# tigor_mbed_rev_b_print.net
KiCad netlist of a schematic drawn in EAGLE
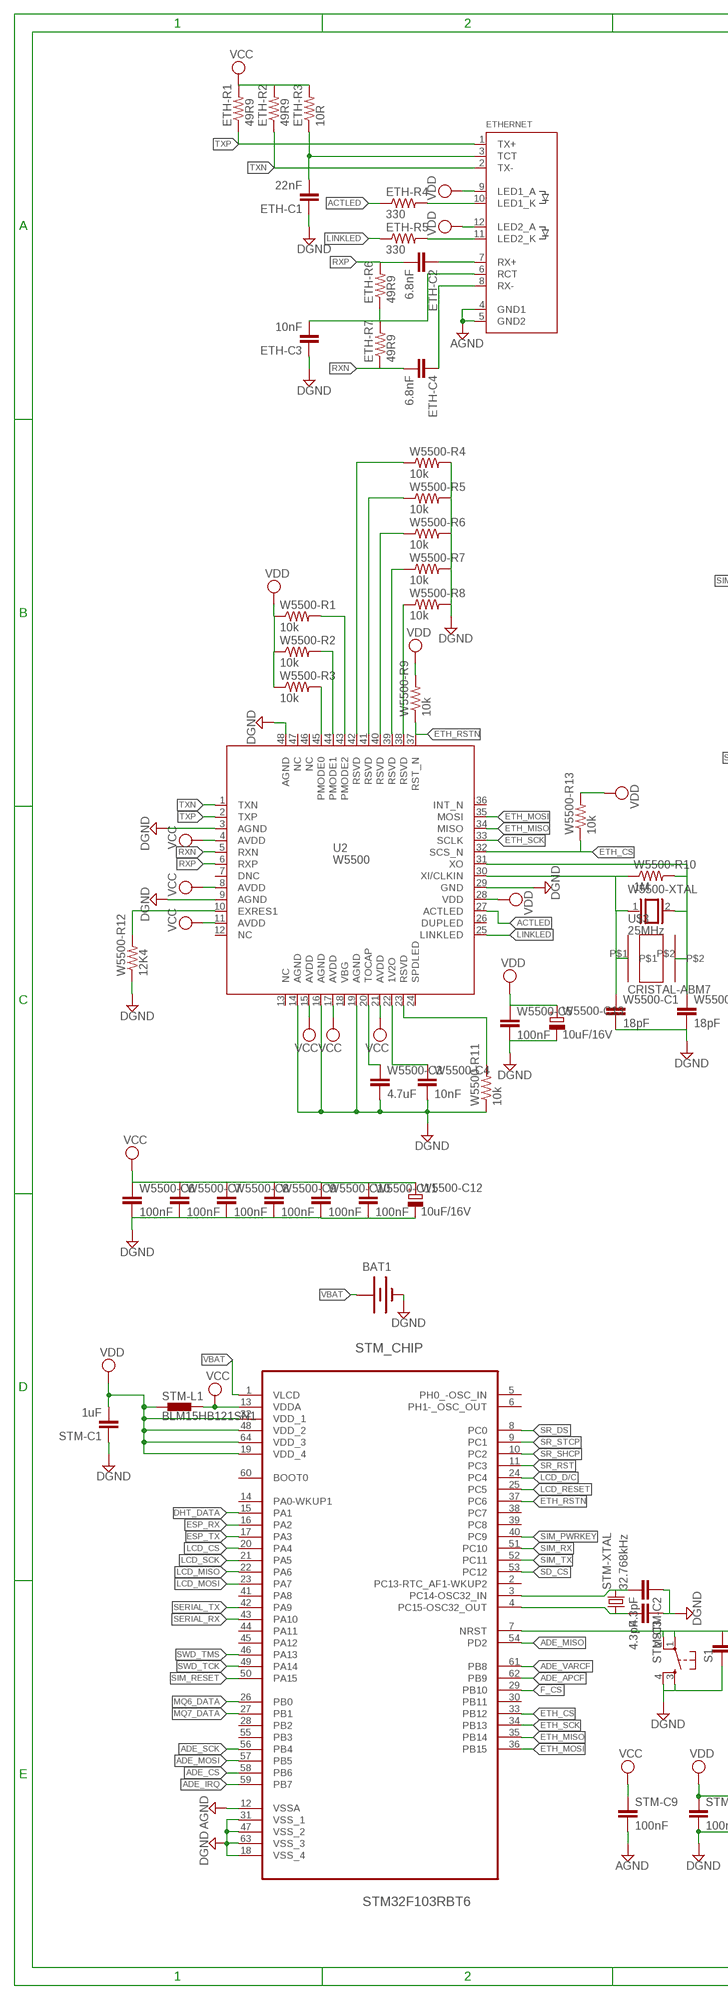
[diagram p0: schematic, sheet 1, part 1 of 2]
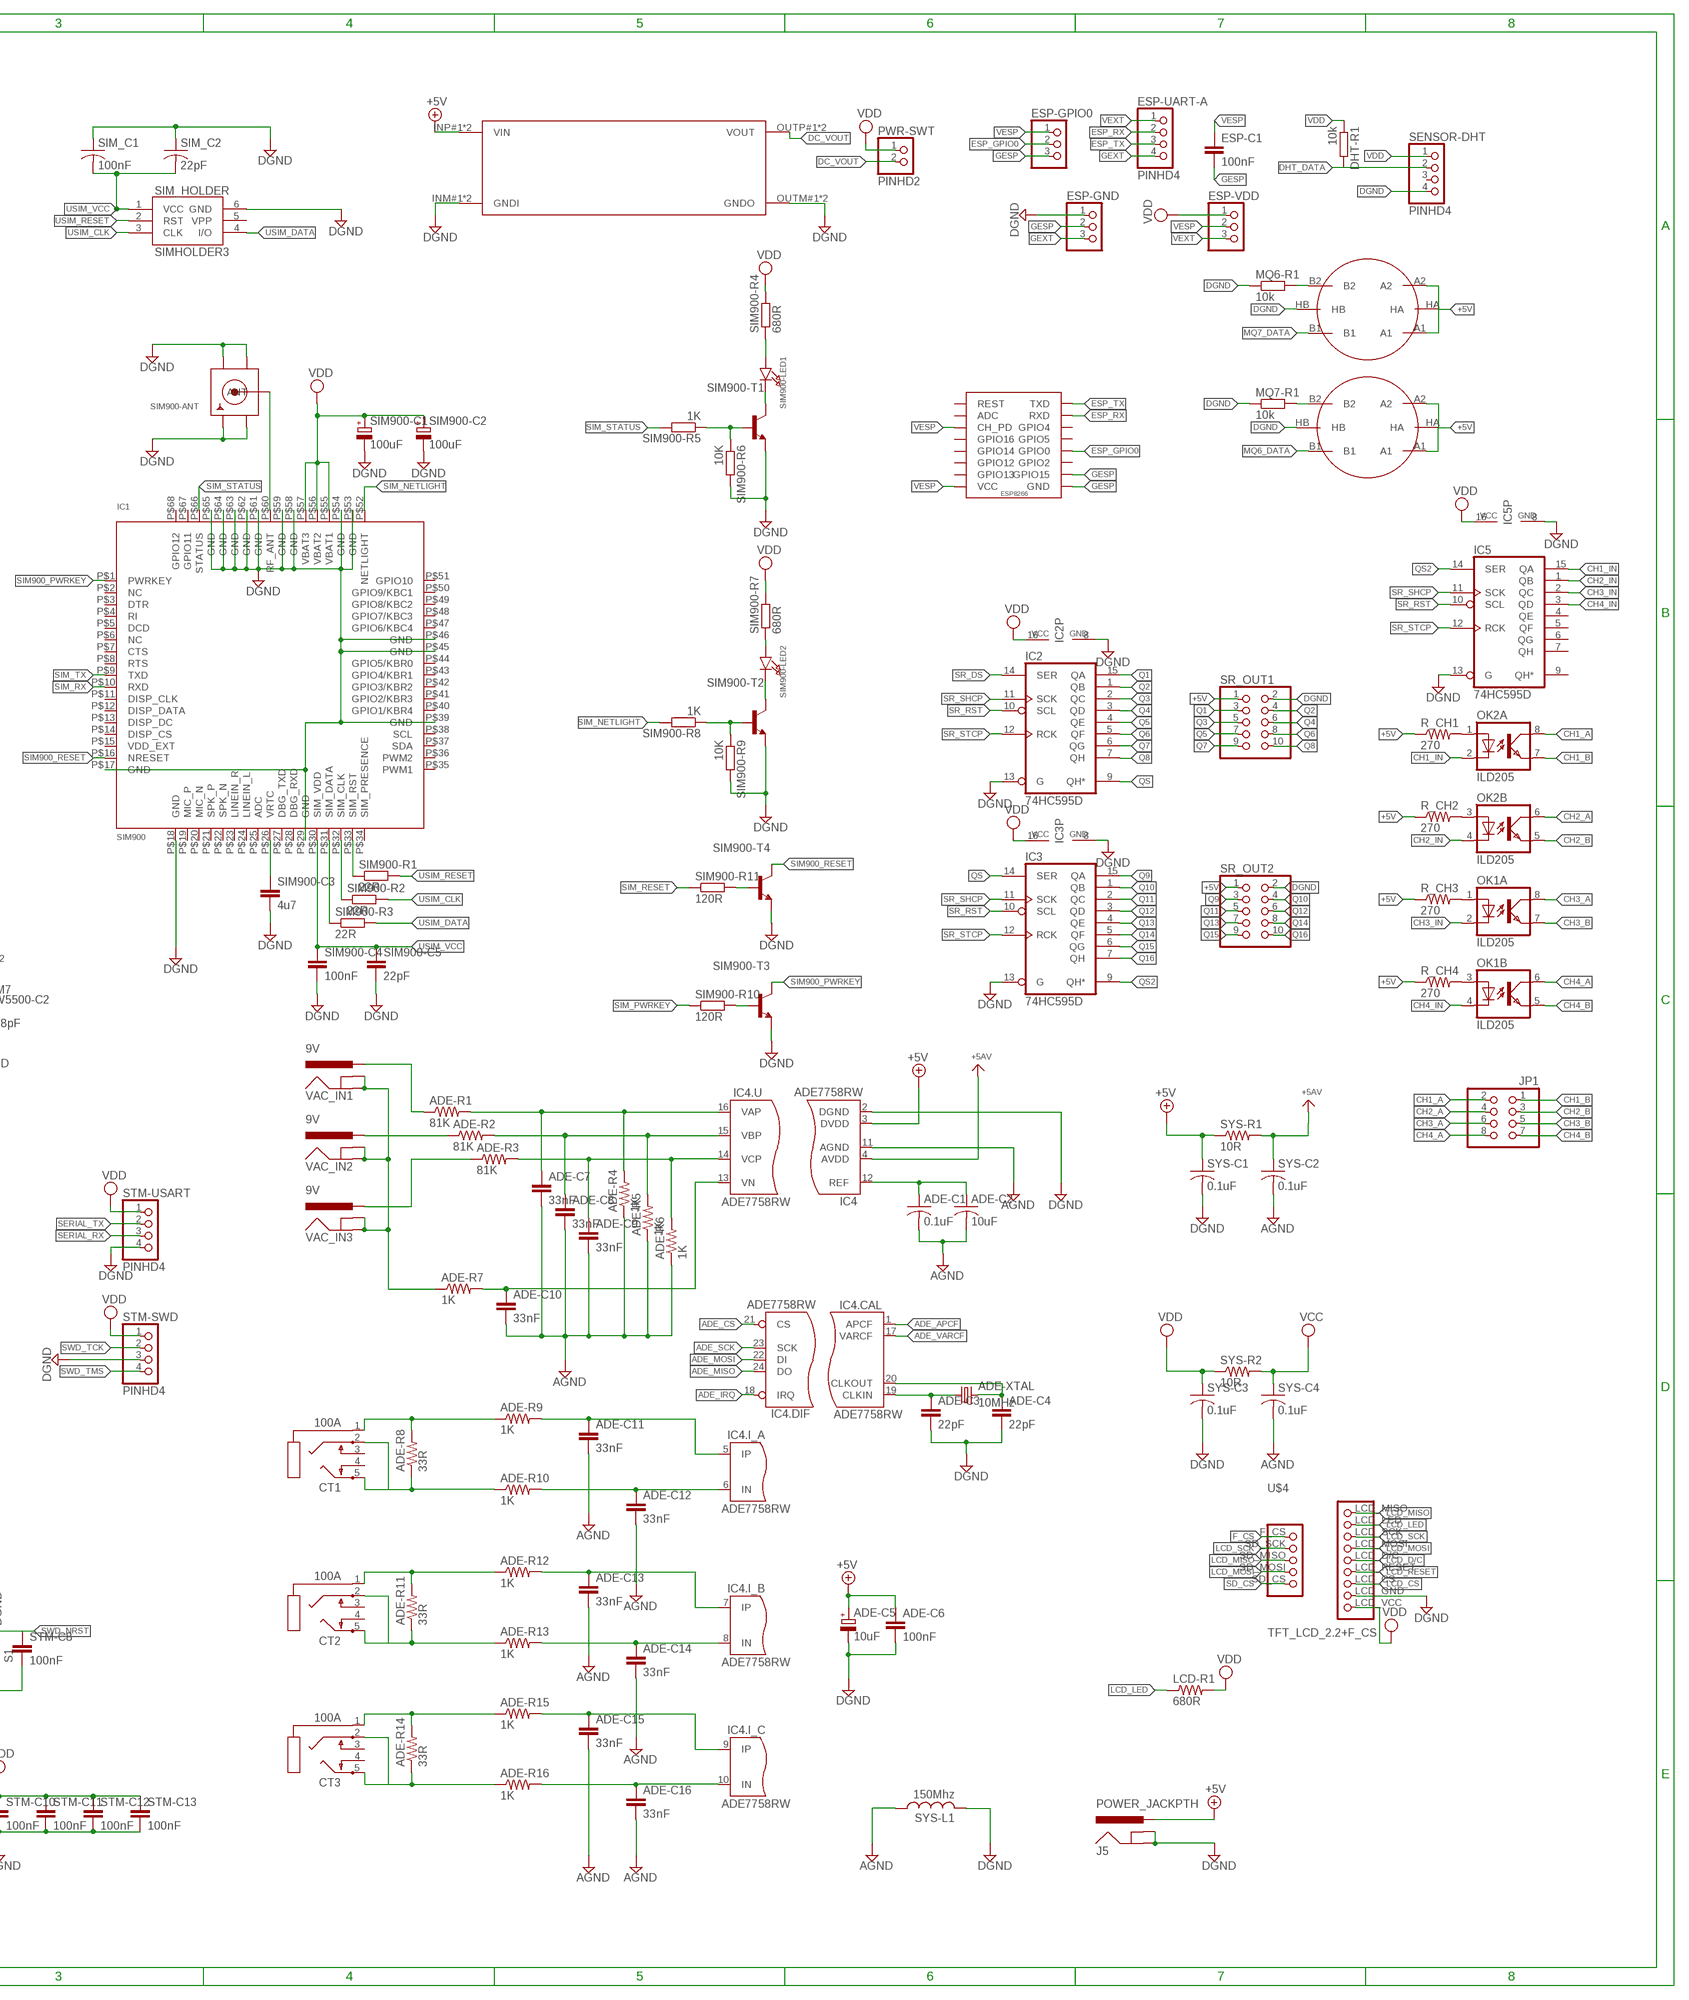
[diagram p1: schematic, sheet 1, part 2 of 2]

(export (version "E")
  (design (tool "Eeschema 10.0.6"))
  (components
    (comp (ref "ADE-C1")
      (value "0.1uF")
      (footprint "eagle-import:C0603@1")
      (libsource (lib "eagle-import") (part "C-USC0603"))
    )
    (comp (ref "ADE-C2")
      (value "10uF")
      (footprint "eagle-import:C0805K")
      (libsource (lib "eagle-import") (part "C-USC0805K"))
    )
    (comp (ref "ADE-C3")
      (value "22pF")
      (footprint "eagle-import:C0603")
      (libsource (lib "eagle-import") (part "C-EUC0603"))
    )
    (comp (ref "ADE-C4")
      (value "22pF")
      (footprint "eagle-import:C0603")
      (libsource (lib "eagle-import") (part "C-EUC0603"))
    )
    (comp (ref "ADE-C5")
      (value "10uF")
      (footprint "eagle-import:153CLV-0605")
      (libsource (lib "eagle-import") (part "CPOL-EU153CLV-0605"))
    )
    (comp (ref "ADE-C6")
      (value "100nF")
      (footprint "eagle-import:C0603")
      (libsource (lib "eagle-import") (part "C-EUC0603"))
    )
    (comp (ref "ADE-C7")
      (value "33nF")
      (footprint "eagle-import:0603-CAP")
      (libsource (lib "eagle-import") (part "CAP0603-CAP"))
    )
    (comp (ref "ADE-C8")
      (value "33nF")
      (footprint "eagle-import:0603-CAP")
      (libsource (lib "eagle-import") (part "CAP0603-CAP"))
    )
    (comp (ref "ADE-C9")
      (value "33nF")
      (footprint "eagle-import:0603-CAP")
      (libsource (lib "eagle-import") (part "CAP0603-CAP"))
    )
    (comp (ref "ADE-C10")
      (value "33nF")
      (footprint "eagle-import:0603-CAP")
      (libsource (lib "eagle-import") (part "CAP0603-CAP"))
    )
    (comp (ref "ADE-C11")
      (value "33nF")
      (footprint "eagle-import:0603-CAP")
      (libsource (lib "eagle-import") (part "CAP0603-CAP"))
    )
    (comp (ref "ADE-C12")
      (value "33nF")
      (footprint "eagle-import:0603-CAP")
      (libsource (lib "eagle-import") (part "CAP0603-CAP"))
    )
    (comp (ref "ADE-C13")
      (value "33nF")
      (footprint "eagle-import:0603-CAP")
      (libsource (lib "eagle-import") (part "CAP0603-CAP"))
    )
    (comp (ref "ADE-C14")
      (value "33nF")
      (footprint "eagle-import:0603-CAP")
      (libsource (lib "eagle-import") (part "CAP0603-CAP"))
    )
    (comp (ref "ADE-C15")
      (value "33nF")
      (footprint "eagle-import:0603-CAP")
      (libsource (lib "eagle-import") (part "CAP0603-CAP"))
    )
    (comp (ref "ADE-C16")
      (value "33nF")
      (footprint "eagle-import:0603-CAP")
      (libsource (lib "eagle-import") (part "CAP0603-CAP"))
    )
    (comp (ref "ADE-R1")
      (value "81K")
      (footprint "eagle-import:0603-RES")
      (libsource (lib "eagle-import") (part "RESISTOR0603-RES"))
    )
    (comp (ref "ADE-R2")
      (value "81K")
      (footprint "eagle-import:0603-RES")
      (libsource (lib "eagle-import") (part "RESISTOR0603-RES"))
    )
    (comp (ref "ADE-R3")
      (value "81K")
      (footprint "eagle-import:0603-RES")
      (libsource (lib "eagle-import") (part "RESISTOR0603-RES"))
    )
    (comp (ref "ADE-R4")
      (value "1K")
      (footprint "eagle-import:0603-RES")
      (libsource (lib "eagle-import") (part "RESISTOR0603-RES"))
    )
    (comp (ref "ADE-R5")
      (value "1K")
      (footprint "eagle-import:0603-RES")
      (libsource (lib "eagle-import") (part "RESISTOR0603-RES"))
    )
    (comp (ref "ADE-R6")
      (value "1K")
      (footprint "eagle-import:0603-RES")
      (libsource (lib "eagle-import") (part "RESISTOR0603-RES"))
    )
    (comp (ref "ADE-R7")
      (value "1K")
      (footprint "eagle-import:0603-RES")
      (libsource (lib "eagle-import") (part "RESISTOR0603-RES"))
    )
    (comp (ref "ADE-R8")
      (value "33R")
      (footprint "eagle-import:0603-RES")
      (libsource (lib "eagle-import") (part "RESISTOR0603-RES"))
    )
    (comp (ref "ADE-R9")
      (value "1K")
      (footprint "eagle-import:0603-RES")
      (libsource (lib "eagle-import") (part "RESISTOR0603-RES"))
    )
    (comp (ref "ADE-R10")
      (value "1K")
      (footprint "eagle-import:0603-RES")
      (libsource (lib "eagle-import") (part "RESISTOR0603-RES"))
    )
    (comp (ref "ADE-R11")
      (value "33R")
      (footprint "eagle-import:0603-RES")
      (libsource (lib "eagle-import") (part "RESISTOR0603-RES"))
    )
    (comp (ref "ADE-R12")
      (value "1K")
      (footprint "eagle-import:0603-RES")
      (libsource (lib "eagle-import") (part "RESISTOR0603-RES"))
    )
    (comp (ref "ADE-R13")
      (value "1K")
      (footprint "eagle-import:0603-RES")
      (libsource (lib "eagle-import") (part "RESISTOR0603-RES"))
    )
    (comp (ref "ADE-R14")
      (value "33R")
      (footprint "eagle-import:0603-RES")
      (libsource (lib "eagle-import") (part "RESISTOR0603-RES"))
    )
    (comp (ref "ADE-R15")
      (value "1K")
      (footprint "eagle-import:0603-RES")
      (libsource (lib "eagle-import") (part "RESISTOR0603-RES"))
    )
    (comp (ref "ADE-R16")
      (value "1K")
      (footprint "eagle-import:0603-RES")
      (libsource (lib "eagle-import") (part "RESISTOR0603-RES"))
    )
    (comp (ref "ADE-XTAL")
      (value "10MHz")
      (footprint "eagle-import:HC49US")
      (libsource (lib "eagle-import") (part "CRYSTALHC49US"))
    )
    (comp (ref "BAT1")
      (value "BATTERY20PTH")
      (footprint "eagle-import:BATTCOM_20MM_PTH")
      (libsource (lib "eagle-import") (part "BATTERY20PTH"))
    )
    (comp (ref "CT1")
      (value "100A")
      (footprint "eagle-import:STX3100")
      (libsource (lib "eagle-import") (part "AUDIO_STEREOJACK"))
    )
    (comp (ref "CT2")
      (value "100A")
      (footprint "eagle-import:STX3100")
      (libsource (lib "eagle-import") (part "AUDIO_STEREOJACK"))
    )
    (comp (ref "CT3")
      (value "100A")
      (footprint "eagle-import:STX3100")
      (libsource (lib "eagle-import") (part "AUDIO_STEREOJACK"))
    )
    (comp (ref "DCDC-3.5V")
      (value "DCDCMODULE_SMALL")
      (footprint "eagle-import:DCDCMODULE-SMALL")
      (libsource (lib "eagle-import") (part "DCDCMODULE_SMALL"))
    )
    (comp (ref "DHT-R1")
      (value "10k")
      (footprint "eagle-import:R0603")
      (libsource (lib "eagle-import") (part "resistor_R-EU_R0603"))
    )
    (comp (ref "ESP-C1")
      (value "100nF")
      (footprint "eagle-import:C0603")
      (libsource (lib "eagle-import") (part "C-EUC0603"))
    )
    (comp (ref "ESP-GND")
      (value "PINHD-1X3")
      (footprint "eagle-import:1X03")
      (libsource (lib "eagle-import") (part "PINHD-1X3"))
    )
    (comp (ref "ESP-GPIO0")
      (value "PINHD-1X3")
      (footprint "eagle-import:1X03")
      (libsource (lib "eagle-import") (part "PINHD-1X3"))
    )
    (comp (ref "ESP-UART-A")
      (value "PINHD4")
      (footprint "eagle-import:PINHD4")
      (libsource (lib "eagle-import") (part "PINHD4"))
    )
    (comp (ref "ESP-VDD")
      (value "PINHD-1X3")
      (footprint "eagle-import:1X03")
      (libsource (lib "eagle-import") (part "PINHD-1X3"))
    )
    (comp (ref "ETH-C1")
      (value "22nF")
      (footprint "eagle-import:C0603")
      (libsource (lib "eagle-import") (part "C-EUC0603"))
    )
    (comp (ref "ETH-C2")
      (value "6.8nF")
      (footprint "eagle-import:C0603")
      (libsource (lib "eagle-import") (part "C-EUC0603"))
    )
    (comp (ref "ETH-C3")
      (value "10nF")
      (footprint "eagle-import:C0603")
      (libsource (lib "eagle-import") (part "C-EUC0603"))
    )
    (comp (ref "ETH-C4")
      (value "6.8nF")
      (footprint "eagle-import:C0603")
      (libsource (lib "eagle-import") (part "C-EUC0603"))
    )
    (comp (ref "ETH-R1")
      (value "49R9")
      (footprint "eagle-import:R0603")
      (libsource (lib "eagle-import") (part "R-US_R0603"))
    )
    (comp (ref "ETH-R2")
      (value "49R9")
      (footprint "eagle-import:R0603")
      (libsource (lib "eagle-import") (part "R-US_R0603"))
    )
    (comp (ref "ETH-R3")
      (value "10R")
      (footprint "eagle-import:R0603")
      (libsource (lib "eagle-import") (part "R-US_R0603"))
    )
    (comp (ref "ETH-R4")
      (value "330")
      (footprint "eagle-import:R0603")
      (libsource (lib "eagle-import") (part "R-US_R0603"))
    )
    (comp (ref "ETH-R5")
      (value "330")
      (footprint "eagle-import:R0603")
      (libsource (lib "eagle-import") (part "R-US_R0603"))
    )
    (comp (ref "ETH-R6")
      (value "49R9")
      (footprint "eagle-import:R0603")
      (libsource (lib "eagle-import") (part "R-US_R0603"))
    )
    (comp (ref "ETH-R7")
      (value "49R9")
      (footprint "eagle-import:R0603")
      (libsource (lib "eagle-import") (part "R-US_R0603"))
    )
    (comp (ref "ETHERNET")
      (value "RJ45J0026D21BNL")
      (footprint "eagle-import:RJ45_PULSEJACK")
      (libsource (lib "eagle-import") (part "RJ45J0026D21BNL"))
    )
    (comp (ref "IC1")
      (value "SIM900")
      (footprint "eagle-import:SIM900_SMT")
      (libsource (lib "eagle-import") (part "GSM_SIM900_LITERAL"))
    )
    (comp (ref "IC2")
      (value "74HC595D")
      (footprint "eagle-import:SO16")
      (libsource (lib "eagle-import") (part "74595DHC"))
    )
    (comp (ref "IC3")
      (value "74HC595D")
      (footprint "eagle-import:SO16")
      (libsource (lib "eagle-import") (part "74595DHC"))
    )
    (comp (ref "IC4")
      (value "ADE7758RW")
      (footprint "eagle-import:SOIC24")
      (libsource (lib "eagle-import") (part "ADE7758RW"))
    )
    (comp (ref "IC5")
      (value "74HC595D")
      (footprint "eagle-import:SO16")
      (libsource (lib "eagle-import") (part "74595DHC"))
    )
    (comp (ref "J5")
      (value "POWER_JACKPTH")
      (footprint "eagle-import:POWER_JACK_PTH")
      (libsource (lib "eagle-import") (part "POWER_JACKPTH"))
    )
    (comp (ref "JP1")
      (value "PINHD-2X4")
      (footprint "eagle-import:2X04")
      (libsource (lib "eagle-import") (part "PINHD-2X4"))
    )
    (comp (ref "LCD-R1")
      (value "680R")
      (footprint "eagle-import:0603-RES")
      (libsource (lib "eagle-import") (part "RESISTOR0603-RES"))
    )
    (comp (ref "MQ6-R1")
      (value "10k")
      (footprint "eagle-import:R0603")
      (libsource (lib "eagle-import") (part "resistor_R-EU_R0603"))
    )
    (comp (ref "MQ7-R1")
      (value "10k")
      (footprint "eagle-import:R0603")
      (libsource (lib "eagle-import") (part "resistor_R-EU_R0603"))
    )
    (comp (ref "OK1")
      (value "ILD205")
      (footprint "eagle-import:SOIC08")
      (fields (field (name "MF") "VISHAY/TELEFUNKEN") (field (name "MPN") "ILD205T"))
      (libsource (lib "eagle-import") (part "ILD205"))
    )
    (comp (ref "OK2")
      (value "ILD205")
      (footprint "eagle-import:SOIC08")
      (fields (field (name "MF") "VISHAY/TELEFUNKEN") (field (name "MPN") "ILD205T"))
      (libsource (lib "eagle-import") (part "ILD205"))
    )
    (comp (ref "PWR-SWT")
      (value "PINHD2")
      (footprint "eagle-import:PINHD2")
      (libsource (lib "eagle-import") (part "PINHD2"))
    )
    (comp (ref "R_CH1")
      (value "270")
      (footprint "eagle-import:0603-RES")
      (libsource (lib "eagle-import") (part "RESISTOR0603-RES"))
    )
    (comp (ref "R_CH2")
      (value "270")
      (footprint "eagle-import:0603-RES")
      (libsource (lib "eagle-import") (part "RESISTOR0603-RES"))
    )
    (comp (ref "R_CH3")
      (value "270")
      (footprint "eagle-import:0603-RES")
      (libsource (lib "eagle-import") (part "RESISTOR0603-RES"))
    )
    (comp (ref "R_CH4")
      (value "270")
      (footprint "eagle-import:0603-RES")
      (libsource (lib "eagle-import") (part "RESISTOR0603-RES"))
    )
    (comp (ref "S1")
      (value "TAC_SWITCHPTH")
      (footprint "eagle-import:TACTILE-PTH")
      (libsource (lib "eagle-import") (part "TAC_SWITCHPTH"))
    )
    (comp (ref "SENSOR-DHT")
      (value "PINHD4")
      (footprint "eagle-import:PINHD4")
      (libsource (lib "eagle-import") (part "PINHD4"))
    )
    (comp (ref "SENSOR-MQ6")
      (value "METHANE_SENSOR")
      (footprint "eagle-import:MQ-3")
      (libsource (lib "eagle-import") (part "METHANE_SENSOR"))
    )
    (comp (ref "SENSOR-MQ7")
      (value "METHANE_SENSOR")
      (footprint "eagle-import:MQ-3")
      (libsource (lib "eagle-import") (part "METHANE_SENSOR"))
    )
    (comp (ref "SIM900-ANT")
      (value "SMACONNECTOR")
      (footprint "eagle-import:SMA90_DIP")
      (libsource (lib "eagle-import") (part "SMACONNECTOR"))
    )
    (comp (ref "SIM900-C1")
      (value "100uF")
      (footprint "eagle-import:153CLV-0605")
      (libsource (lib "eagle-import") (part "CPOL-EU153CLV-0605"))
    )
    (comp (ref "SIM900-C2")
      (value "100uF")
      (footprint "eagle-import:153CLV-0605")
      (libsource (lib "eagle-import") (part "CPOL-EU153CLV-0605"))
    )
    (comp (ref "SIM900-C3")
      (value "4u7")
      (footprint "eagle-import:C0603")
      (libsource (lib "eagle-import") (part "C-EUC0603"))
    )
    (comp (ref "SIM900-C4")
      (value "100nF")
      (footprint "eagle-import:C0603")
      (libsource (lib "eagle-import") (part "C-EUC0603"))
    )
    (comp (ref "SIM900-C5")
      (value "22pF")
      (footprint "eagle-import:C0603")
      (libsource (lib "eagle-import") (part "C-EUC0603"))
    )
    (comp (ref "SIM900-LED1")
      (value "LED0805_NOOUTLINE")
      (footprint "eagle-import:CHIPLED_0805_NOOUTLINE")
      (libsource (lib "eagle-import") (part "LED0805_NOOUTLINE"))
    )
    (comp (ref "SIM900-LED2")
      (value "LED0805_NOOUTLINE")
      (footprint "eagle-import:CHIPLED_0805_NOOUTLINE")
      (libsource (lib "eagle-import") (part "LED0805_NOOUTLINE"))
    )
    (comp (ref "SIM900-R1")
      (value "22R")
      (footprint "eagle-import:R0603")
      (libsource (lib "eagle-import") (part "R-EU_R0603"))
    )
    (comp (ref "SIM900-R2")
      (value "22R")
      (footprint "eagle-import:R0603")
      (libsource (lib "eagle-import") (part "R-EU_R0603"))
    )
    (comp (ref "SIM900-R3")
      (value "22R")
      (footprint "eagle-import:R0603")
      (libsource (lib "eagle-import") (part "R-EU_R0603"))
    )
    (comp (ref "SIM900-R4")
      (value "680R")
      (footprint "eagle-import:R0603")
      (libsource (lib "eagle-import") (part "R-EU_R0603"))
    )
    (comp (ref "SIM900-R5")
      (value "1K")
      (footprint "eagle-import:R0603")
      (libsource (lib "eagle-import") (part "R-EU_R0603"))
    )
    (comp (ref "SIM900-R6")
      (value "10K")
      (footprint "eagle-import:R0603")
      (libsource (lib "eagle-import") (part "R-EU_R0603"))
    )
    (comp (ref "SIM900-R7")
      (value "680R")
      (footprint "eagle-import:R0603")
      (libsource (lib "eagle-import") (part "R-EU_R0603"))
    )
    (comp (ref "SIM900-R8")
      (value "1K")
      (footprint "eagle-import:R0603")
      (libsource (lib "eagle-import") (part "R-EU_R0603"))
    )
    (comp (ref "SIM900-R9")
      (value "10K")
      (footprint "eagle-import:R0603")
      (libsource (lib "eagle-import") (part "R-EU_R0603"))
    )
    (comp (ref "SIM900-R10")
      (value "120R")
      (footprint "eagle-import:R0603")
      (libsource (lib "eagle-import") (part "resistor_R-EU_R0603"))
    )
    (comp (ref "SIM900-R11")
      (value "120R")
      (footprint "eagle-import:R0603")
      (libsource (lib "eagle-import") (part "resistor_R-EU_R0603"))
    )
    (comp (ref "SIM900-T1")
      (value "MMBT2222ALT1-NPN-SOT23-BEC")
      (footprint "eagle-import:SOT23-BEC")
      (libsource (lib "eagle-import") (part "-NPN-SOT23-BECMMBT2222ALT1"))
    )
    (comp (ref "SIM900-T2")
      (value "MMBT2222ALT1-NPN-SOT23-BEC")
      (footprint "eagle-import:SOT23-BEC")
      (libsource (lib "eagle-import") (part "-NPN-SOT23-BECMMBT2222ALT1"))
    )
    (comp (ref "SIM900-T3")
      (value "MMBT2222ALT1-NPN-SOT23-BEC")
      (footprint "eagle-import:SOT23-BEC")
      (libsource (lib "eagle-import") (part "transistor-neu-to92_-NPN-SOT23-BECMMBT2222ALT1"))
    )
    (comp (ref "SIM900-T4")
      (value "MMBT2222ALT1-NPN-SOT23-BEC")
      (footprint "eagle-import:SOT23-BEC")
      (libsource (lib "eagle-import") (part "transistor-neu-to92_-NPN-SOT23-BECMMBT2222ALT1"))
    )
    (comp (ref "SIM_C1")
      (value "100nF")
      (footprint "eagle-import:C0603K")
      (libsource (lib "eagle-import") (part "C-USC0603K"))
    )
    (comp (ref "SIM_C2")
      (value "22pF")
      (footprint "eagle-import:C0603K")
      (libsource (lib "eagle-import") (part "C-USC0603K"))
    )
    (comp (ref "SIM_HOLDER")
      (value "SIMHOLDER3")
      (footprint "eagle-import:SIMHOLDER3")
      (libsource (lib "eagle-import") (part "SIMHOLDER3"))
    )
    (comp (ref "SR_OUT1")
      (value "PINHD-2X5/90")
      (footprint "eagle-import:2X05_90")
      (libsource (lib "eagle-import") (part "PINHD-2X5/90"))
    )
    (comp (ref "SR_OUT2")
      (value "PINHD-2X5/90")
      (footprint "eagle-import:2X05_90")
      (libsource (lib "eagle-import") (part "PINHD-2X5/90"))
    )
    (comp (ref "STM-C1")
      (value "1uF")
      (footprint "eagle-import:C0603")
      (libsource (lib "eagle-import") (part "C-EUC0603"))
    )
    (comp (ref "STM-C2")
      (value "4.3pF")
      (footprint "eagle-import:C0603")
      (libsource (lib "eagle-import") (part "C-EUC0603"))
    )
    (comp (ref "STM-C3")
      (value "4.3pF")
      (footprint "eagle-import:C0603")
      (libsource (lib "eagle-import") (part "C-EUC0603"))
    )
    (comp (ref "STM-C8")
      (value "100nF")
      (footprint "eagle-import:C0603")
      (libsource (lib "eagle-import") (part "C-EUC0603"))
    )
    (comp (ref "STM-C9")
      (value "100nF")
      (footprint "eagle-import:C0603")
      (libsource (lib "eagle-import") (part "C-EUC0603"))
    )
    (comp (ref "STM-C10")
      (value "100nF")
      (footprint "eagle-import:C0603")
      (libsource (lib "eagle-import") (part "C-EUC0603"))
    )
    (comp (ref "STM-C11")
      (value "100nF")
      (footprint "eagle-import:C0603")
      (libsource (lib "eagle-import") (part "C-EUC0603"))
    )
    (comp (ref "STM-C12")
      (value "100nF")
      (footprint "eagle-import:C0603")
      (libsource (lib "eagle-import") (part "C-EUC0603"))
    )
    (comp (ref "STM-C13")
      (value "100nF")
      (footprint "eagle-import:C0603")
      (libsource (lib "eagle-import") (part "C-EUC0603"))
    )
    (comp (ref "STM-L1")
      (value "BLM15HB121SN1")
      (footprint "eagle-import:0402")
      (libsource (lib "eagle-import") (part "BLM15HB121SN1"))
    )
    (comp (ref "STM-SWD")
      (value "PINHD4")
      (footprint "eagle-import:PINHD4")
      (libsource (lib "eagle-import") (part "PINHD4"))
    )
    (comp (ref "STM-USART")
      (value "PINHD4")
      (footprint "eagle-import:PINHD4")
      (libsource (lib "eagle-import") (part "PINHD4"))
    )
    (comp (ref "STM-XTAL")
      (value "32.768kHz")
      (footprint "eagle-import:TC26H")
      (libsource (lib "eagle-import") (part "CRYSTALTC26H"))
    )
    (comp (ref "STM_CHIP")
      (value "STM32F103RBT6")
      (footprint "eagle-import:QFP50P1200X1200X160-64N")
      (fields (field (name "MPN") "STM32L152RBT6"))
      (libsource (lib "eagle-import") (part "STM32L152RBT6"))
    )
    (comp (ref "SYS-C1")
      (value "0.1uF")
      (footprint "eagle-import:C0603@1")
      (libsource (lib "eagle-import") (part "C-USC0603"))
    )
    (comp (ref "SYS-C2")
      (value "0.1uF")
      (footprint "eagle-import:C0603@1")
      (libsource (lib "eagle-import") (part "C-USC0603"))
    )
    (comp (ref "SYS-C3")
      (value "0.1uF")
      (footprint "eagle-import:C0603@1")
      (libsource (lib "eagle-import") (part "C-USC0603"))
    )
    (comp (ref "SYS-C4")
      (value "0.1uF")
      (footprint "eagle-import:C0603@1")
      (libsource (lib "eagle-import") (part "C-USC0603"))
    )
    (comp (ref "SYS-L1")
      (value "150Mhz")
      (footprint "eagle-import:POWER-CHOKE_WE-TPC")
      (libsource (lib "eagle-import") (part "L-USWE-TPC"))
    )
    (comp (ref "SYS-R1")
      (value "10R")
      (footprint "eagle-import:0603-RES")
      (libsource (lib "eagle-import") (part "RESISTOR0603-RES"))
    )
    (comp (ref "SYS-R2")
      (value "10R")
      (footprint "eagle-import:0603-RES")
      (libsource (lib "eagle-import") (part "RESISTOR0603-RES"))
    )
    (comp (ref "U$3")
      (value "CRISTAL-ABM7")
      (footprint "eagle-import:CRISTAL-ABM7")
      (libsource (lib "eagle-import") (part "CRISTAL-ABM7"))
    )
    (comp (ref "U$4")
      (value "TFT_LCD_2.2+F_CS")
      (footprint "eagle-import:TFT_LCD_2.2+F_CS")
      (libsource (lib "eagle-import") (part "TFT_LCD_2.2+F_CS"))
    )
    (comp (ref "U$5")
      (value "ESP8266WI12")
      (footprint "eagle-import:WI12")
      (libsource (lib "eagle-import") (part "ESP8266WI12"))
    )
    (comp (ref "U2")
      (value "W5500")
      (footprint "eagle-import:W5500")
      (libsource (lib "eagle-import") (part "W5500"))
    )
    (comp (ref "VAC_IN1")
      (value "9V")
      (footprint "eagle-import:POWER_JACK_PTH")
      (libsource (lib "eagle-import") (part "POWER_JACKPTH"))
    )
    (comp (ref "VAC_IN2")
      (value "9V")
      (footprint "eagle-import:POWER_JACK_PTH")
      (libsource (lib "eagle-import") (part "POWER_JACKPTH"))
    )
    (comp (ref "VAC_IN3")
      (value "9V")
      (footprint "eagle-import:POWER_JACK_PTH")
      (libsource (lib "eagle-import") (part "POWER_JACKPTH"))
    )
    (comp (ref "W5500-C1")
      (value "18pF")
      (footprint "eagle-import:C0603")
      (libsource (lib "eagle-import") (part "C-EUC0603"))
    )
    (comp (ref "W5500-C2")
      (value "18pF")
      (footprint "eagle-import:C0603")
      (libsource (lib "eagle-import") (part "C-EUC0603"))
    )
    (comp (ref "W5500-C3")
      (value "4.7uF")
      (footprint "eagle-import:C0603")
      (libsource (lib "eagle-import") (part "C-EUC0603"))
    )
    (comp (ref "W5500-C4")
      (value "10nF")
      (footprint "eagle-import:C0603")
      (libsource (lib "eagle-import") (part "C-EUC0603"))
    )
    (comp (ref "W5500-C5")
      (value "100nF")
      (footprint "eagle-import:C0603")
      (libsource (lib "eagle-import") (part "C-EUC0603"))
    )
    (comp (ref "W5500-C6")
      (value "100nF")
      (footprint "eagle-import:C0603")
      (libsource (lib "eagle-import") (part "C-EUC0603"))
    )
    (comp (ref "W5500-C7")
      (value "100nF")
      (footprint "eagle-import:C0603")
      (libsource (lib "eagle-import") (part "C-EUC0603"))
    )
    (comp (ref "W5500-C8")
      (value "100nF")
      (footprint "eagle-import:C0603")
      (libsource (lib "eagle-import") (part "C-EUC0603"))
    )
    (comp (ref "W5500-C9")
      (value "100nF")
      (footprint "eagle-import:C0603")
      (libsource (lib "eagle-import") (part "C-EUC0603"))
    )
    (comp (ref "W5500-C10")
      (value "100nF")
      (footprint "eagle-import:C0603")
      (libsource (lib "eagle-import") (part "C-EUC0603"))
    )
    (comp (ref "W5500-C11")
      (value "100nF")
      (footprint "eagle-import:C0603")
      (libsource (lib "eagle-import") (part "C-EUC0603"))
    )
    (comp (ref "W5500-C12")
      (value "10uF/16V")
      (footprint "eagle-import:153CLV-0605")
      (libsource (lib "eagle-import") (part "CPOL-EU153CLV-0605"))
    )
    (comp (ref "W5500-C13")
      (value "10uF/16V")
      (footprint "eagle-import:153CLV-0605")
      (libsource (lib "eagle-import") (part "CPOL-EU153CLV-0605"))
    )
    (comp (ref "W5500-R1")
      (value "10k")
      (footprint "eagle-import:R0603")
      (libsource (lib "eagle-import") (part "R-US_R0603"))
    )
    (comp (ref "W5500-R2")
      (value "10k")
      (footprint "eagle-import:R0603")
      (libsource (lib "eagle-import") (part "R-US_R0603"))
    )
    (comp (ref "W5500-R3")
      (value "10k")
      (footprint "eagle-import:R0603")
      (libsource (lib "eagle-import") (part "R-US_R0603"))
    )
    (comp (ref "W5500-R4")
      (value "10k")
      (footprint "eagle-import:R0603")
      (libsource (lib "eagle-import") (part "R-US_R0603"))
    )
    (comp (ref "W5500-R5")
      (value "10k")
      (footprint "eagle-import:R0603")
      (libsource (lib "eagle-import") (part "R-US_R0603"))
    )
    (comp (ref "W5500-R6")
      (value "10k")
      (footprint "eagle-import:R0603")
      (libsource (lib "eagle-import") (part "R-US_R0603"))
    )
    (comp (ref "W5500-R7")
      (value "10k")
      (footprint "eagle-import:R0603")
      (libsource (lib "eagle-import") (part "R-US_R0603"))
    )
    (comp (ref "W5500-R8")
      (value "10k")
      (footprint "eagle-import:R0603")
      (libsource (lib "eagle-import") (part "R-US_R0603"))
    )
    (comp (ref "W5500-R9")
      (value "10k")
      (footprint "eagle-import:R0603")
      (libsource (lib "eagle-import") (part "R-US_R0603"))
    )
    (comp (ref "W5500-R10")
      (value "1M")
      (footprint "eagle-import:R0603")
      (libsource (lib "eagle-import") (part "R-US_R0603"))
    )
    (comp (ref "W5500-R11")
      (value "10k")
      (footprint "eagle-import:R0603")
      (libsource (lib "eagle-import") (part "R-US_R0603"))
    )
    (comp (ref "W5500-R12")
      (value "12K4")
      (footprint "eagle-import:R0805")
      (libsource (lib "eagle-import") (part "R-US_R0805"))
    )
    (comp (ref "W5500-R13")
      (value "10k")
      (footprint "eagle-import:R0603")
      (libsource (lib "eagle-import") (part "R-US_R0603"))
    )
    (comp (ref "W5500-XTAL")
      (value "25MHz")
      (footprint "eagle-import:QS")
      (libsource (lib "eagle-import") (part "XTAL/S"))
    )
  )
  (nets
    (net (code "1") (name "+5AV") (class "Default")
      (node (ref "IC4") (pin "4") (pinfunction "AVDD_4") (pintype "power_in"))
      (node (ref "SYS-C2") (pin "1") (pinfunction "1_1") (pintype "passive"))
      (node (ref "SYS-R1") (pin "2") (pinfunction "2_2") (pintype "passive"))
    )
    (net (code "2") (name "+5V") (class "Default")
      (node (ref "ADE-C5") (pin "+") (pinfunction "+_+") (pintype "passive"))
      (node (ref "ADE-C6") (pin "1") (pinfunction "1_1") (pintype "passive"))
      (node (ref "DCDC-3.5V") (pin "INP#1") (pinfunction "VIN_INP#1") (pintype "bidirectional"))
      (node (ref "DCDC-3.5V") (pin "INP#2") (pinfunction "VIN_INP#2") (pintype "bidirectional"))
      (node (ref "IC4") (pin "3") (pinfunction "DVDD_3") (pintype "power_in"))
      (node (ref "J5") (pin "PWR") (pinfunction "PWR_PWR") (pintype "bidirectional"))
      (node (ref "R_CH1") (pin "1") (pinfunction "1_1") (pintype "passive"))
      (node (ref "R_CH2") (pin "1") (pinfunction "1_1") (pintype "passive"))
      (node (ref "R_CH3") (pin "1") (pinfunction "1_1") (pintype "passive"))
      (node (ref "R_CH4") (pin "1") (pinfunction "1_1") (pintype "passive"))
      (node (ref "SENSOR-MQ6") (pin "A1") (pinfunction "A1_A1") (pintype "bidirectional"))
      (node (ref "SENSOR-MQ6") (pin "A2") (pinfunction "A2_A2") (pintype "bidirectional"))
      (node (ref "SENSOR-MQ6") (pin "HA") (pinfunction "HA_HA") (pintype "bidirectional"))
      (node (ref "SENSOR-MQ7") (pin "A1") (pinfunction "A1_A1") (pintype "bidirectional"))
      (node (ref "SENSOR-MQ7") (pin "A2") (pinfunction "A2_A2") (pintype "bidirectional"))
      (node (ref "SENSOR-MQ7") (pin "HA") (pinfunction "HA_HA") (pintype "bidirectional"))
      (node (ref "SR_OUT1") (pin "1") (pinfunction "1_1") (pintype "passive"))
      (node (ref "SR_OUT2") (pin "1") (pinfunction "1_1") (pintype "passive"))
      (node (ref "SYS-C1") (pin "1") (pinfunction "1_1") (pintype "passive"))
      (node (ref "SYS-R1") (pin "1") (pinfunction "1_1") (pintype "passive"))
    )
    (net (code "3") (name "/GPIO11") (class "Default")
      (node (ref "IC1") (pin "P$67") (pinfunction "GPIO11_P$67") (pintype "power_in"))
    )
    (net (code "4") (name "/GPIO12") (class "Default")
      (node (ref "IC1") (pin "P$68") (pinfunction "GPIO12_P$68") (pintype "power_in"))
    )
    (net (code "5") (name "ACTLED") (class "Default")
      (node (ref "ETH-R4") (pin "1") (pinfunction "1_1") (pintype "passive"))
      (node (ref "U2") (pin "27") (pinfunction "ACTLED_27") (pintype "passive"))
    )
    (net (code "6") (name "ADE_APCF") (class "Default")
      (node (ref "IC4") (pin "1") (pinfunction "APCF_1") (pintype "output"))
      (node (ref "STM_CHIP") (pin "62") (pinfunction "PB9_62") (pintype "bidirectional"))
    )
    (net (code "7") (name "ADE_CS") (class "Default")
      (node (ref "IC4") (pin "21") (pinfunction "CS_21") (pintype "input"))
      (node (ref "STM_CHIP") (pin "58") (pinfunction "PB6_58") (pintype "bidirectional"))
    )
    (net (code "8") (name "ADE_IRQ") (class "Default")
      (node (ref "IC4") (pin "18") (pinfunction "IRQ_18") (pintype "output"))
      (node (ref "STM_CHIP") (pin "59") (pinfunction "PB7_59") (pintype "bidirectional"))
    )
    (net (code "9") (name "ADE_MISO") (class "Default")
      (node (ref "IC4") (pin "24") (pinfunction "DO_24") (pintype "output"))
      (node (ref "STM_CHIP") (pin "54") (pinfunction "PD2_54") (pintype "bidirectional"))
    )
    (net (code "10") (name "ADE_MOSI") (class "Default")
      (node (ref "IC4") (pin "22") (pinfunction "DI_22") (pintype "input"))
      (node (ref "STM_CHIP") (pin "57") (pinfunction "PB5_57") (pintype "bidirectional"))
    )
    (net (code "11") (name "ADE_SCK") (class "Default")
      (node (ref "IC4") (pin "23") (pinfunction "SCK_23") (pintype "input"))
      (node (ref "STM_CHIP") (pin "56") (pinfunction "PB4_56") (pintype "bidirectional"))
    )
    (net (code "12") (name "ADE_VARCF") (class "Default")
      (node (ref "IC4") (pin "17") (pinfunction "VARCF_17") (pintype "output"))
      (node (ref "STM_CHIP") (pin "61") (pinfunction "PB8_61") (pintype "bidirectional"))
    )
    (net (code "13") (name "AGND") (class "Default")
      (node (ref "ADE-C1") (pin "2") (pinfunction "2_2") (pintype "passive"))
      (node (ref "ADE-C10") (pin "2") (pinfunction "2_2") (pintype "passive"))
      (node (ref "ADE-C11") (pin "2") (pinfunction "2_2") (pintype "passive"))
      (node (ref "ADE-C12") (pin "2") (pinfunction "2_2") (pintype "passive"))
      (node (ref "ADE-C13") (pin "2") (pinfunction "2_2") (pintype "passive"))
      (node (ref "ADE-C14") (pin "2") (pinfunction "2_2") (pintype "passive"))
      (node (ref "ADE-C15") (pin "2") (pinfunction "2_2") (pintype "passive"))
      (node (ref "ADE-C16") (pin "2") (pinfunction "2_2") (pintype "passive"))
      (node (ref "ADE-C2") (pin "2") (pinfunction "2_2") (pintype "passive"))
      (node (ref "ADE-C7") (pin "2") (pinfunction "2_2") (pintype "passive"))
      (node (ref "ADE-C8") (pin "2") (pinfunction "2_2") (pintype "passive"))
      (node (ref "ADE-C9") (pin "2") (pinfunction "2_2") (pintype "passive"))
      (node (ref "ADE-R4") (pin "1") (pinfunction "1_1") (pintype "passive"))
      (node (ref "ADE-R5") (pin "1") (pinfunction "1_1") (pintype "passive"))
      (node (ref "ADE-R6") (pin "1") (pinfunction "1_1") (pintype "passive"))
      (node (ref "ETHERNET") (pin "4") (pinfunction "GND1_4") (pintype "bidirectional"))
      (node (ref "ETHERNET") (pin "5") (pinfunction "GND2_5") (pintype "bidirectional"))
      (node (ref "IC4") (pin "11") (pinfunction "AGND_11") (pintype "power_in"))
      (node (ref "STM-C9") (pin "2") (pinfunction "2_2") (pintype "passive"))
      (node (ref "STM_CHIP") (pin "12") (pinfunction "VSSA_12") (pintype "power_in"))
      (node (ref "SYS-C2") (pin "2") (pinfunction "2_2") (pintype "passive"))
      (node (ref "SYS-C4") (pin "2") (pinfunction "2_2") (pintype "passive"))
      (node (ref "SYS-L1") (pin "1") (pinfunction "1_1") (pintype "passive"))
    )
    (net (code "14") (name "CH1_A") (class "Default")
      (node (ref "JP1") (pin "2") (pinfunction "2_2") (pintype "passive"))
      (node (ref "OK2") (pin "8") (pinfunction "COL_8") (pintype "passive"))
    )
    (net (code "15") (name "CH1_B") (class "Default")
      (node (ref "JP1") (pin "1") (pinfunction "1_1") (pintype "passive"))
      (node (ref "OK2") (pin "7") (pinfunction "EMIT_7") (pintype "passive"))
    )
    (net (code "16") (name "CH1_IN") (class "Default")
      (node (ref "IC5") (pin "15") (pinfunction "QA_15") (pintype "tri_state"))
      (node (ref "OK2") (pin "2") (pinfunction "C_2") (pintype "passive"))
    )
    (net (code "17") (name "CH2_A") (class "Default")
      (node (ref "JP1") (pin "4") (pinfunction "4_4") (pintype "passive"))
      (node (ref "OK2") (pin "6") (pinfunction "COL_6") (pintype "passive"))
    )
    (net (code "18") (name "CH2_B") (class "Default")
      (node (ref "JP1") (pin "3") (pinfunction "3_3") (pintype "passive"))
      (node (ref "OK2") (pin "5") (pinfunction "EMIT_5") (pintype "passive"))
    )
    (net (code "19") (name "CH2_IN") (class "Default")
      (node (ref "IC5") (pin "1") (pinfunction "QB_1") (pintype "tri_state"))
      (node (ref "OK2") (pin "4") (pinfunction "C_4") (pintype "passive"))
    )
    (net (code "20") (name "CH3_A") (class "Default")
      (node (ref "JP1") (pin "6") (pinfunction "6_6") (pintype "passive"))
      (node (ref "OK1") (pin "8") (pinfunction "COL_8") (pintype "passive"))
    )
    (net (code "21") (name "CH3_B") (class "Default")
      (node (ref "JP1") (pin "5") (pinfunction "5_5") (pintype "passive"))
      (node (ref "OK1") (pin "7") (pinfunction "EMIT_7") (pintype "passive"))
    )
    (net (code "22") (name "CH3_IN") (class "Default")
      (node (ref "IC5") (pin "2") (pinfunction "QC_2") (pintype "tri_state"))
      (node (ref "OK1") (pin "2") (pinfunction "C_2") (pintype "passive"))
    )
    (net (code "23") (name "CH4_A") (class "Default")
      (node (ref "JP1") (pin "8") (pinfunction "8_8") (pintype "passive"))
      (node (ref "OK1") (pin "6") (pinfunction "COL_6") (pintype "passive"))
    )
    (net (code "24") (name "CH4_B") (class "Default")
      (node (ref "JP1") (pin "7") (pinfunction "7_7") (pintype "passive"))
      (node (ref "OK1") (pin "5") (pinfunction "EMIT_5") (pintype "passive"))
    )
    (net (code "25") (name "CH4_IN") (class "Default")
      (node (ref "IC5") (pin "3") (pinfunction "QD_3") (pintype "tri_state"))
      (node (ref "OK1") (pin "4") (pinfunction "C_4") (pintype "passive"))
    )
    (net (code "26") (name "DC_VOUT") (class "Default")
      (node (ref "DCDC-3.5V") (pin "OUTP#1") (pinfunction "VOUT_OUTP#1") (pintype "bidirectional"))
      (node (ref "DCDC-3.5V") (pin "OUTP#2") (pinfunction "VOUT_OUTP#2") (pintype "bidirectional"))
      (node (ref "PWR-SWT") (pin "2") (pinfunction "2_2") (pintype "passive"))
    )
    (net (code "27") (name "DGND") (class "Default")
      (node (ref "ADE-C3") (pin "2") (pinfunction "2_2") (pintype "passive"))
      (node (ref "ADE-C4") (pin "2") (pinfunction "2_2") (pintype "passive"))
      (node (ref "ADE-C5") (pin "-") (pinfunction "-_-") (pintype "passive"))
      (node (ref "ADE-C6") (pin "2") (pinfunction "2_2") (pintype "passive"))
      (node (ref "BAT1") (pin "2") (pinfunction "-_2") (pintype "power_in"))
      (node (ref "DCDC-3.5V") (pin "INM#1") (pinfunction "GNDI_INM#1") (pintype "bidirectional"))
      (node (ref "DCDC-3.5V") (pin "INM#2") (pinfunction "GNDI_INM#2") (pintype "bidirectional"))
      (node (ref "DCDC-3.5V") (pin "OUTM#1") (pinfunction "GNDO_OUTM#1") (pintype "bidirectional"))
      (node (ref "DCDC-3.5V") (pin "OUTM#2") (pinfunction "GNDO_OUTM#2") (pintype "bidirectional"))
      (node (ref "ESP-GND") (pin "1") (pinfunction "1_1") (pintype "passive"))
      (node (ref "ETH-C1") (pin "1") (pinfunction "1_1") (pintype "passive"))
      (node (ref "ETH-C3") (pin "1") (pinfunction "1_1") (pintype "passive"))
      (node (ref "IC1") (pin "P$17") (pinfunction "GND_P$17") (pintype "power_in"))
      (node (ref "IC1") (pin "P$18") (pinfunction "GND_P$18") (pintype "power_in"))
      (node (ref "IC1") (pin "P$29") (pinfunction "GND_P$29") (pintype "power_in"))
      (node (ref "IC1") (pin "P$39") (pinfunction "GND_P$39") (pintype "power_in"))
      (node (ref "IC1") (pin "P$45") (pinfunction "GND_P$45") (pintype "power_in"))
      (node (ref "IC1") (pin "P$46") (pinfunction "GND_P$46") (pintype "power_in"))
      (node (ref "IC1") (pin "P$53") (pinfunction "GND_P$53") (pintype "power_in"))
      (node (ref "IC1") (pin "P$54") (pinfunction "GND_P$54") (pintype "power_in"))
      (node (ref "IC1") (pin "P$58") (pinfunction "GND_P$58") (pintype "power_in"))
      (node (ref "IC1") (pin "P$59") (pinfunction "GND_P$59") (pintype "power_in"))
      (node (ref "IC1") (pin "P$61") (pinfunction "GND_P$61") (pintype "power_in"))
      (node (ref "IC1") (pin "P$62") (pinfunction "GND_P$62") (pintype "power_in"))
      (node (ref "IC1") (pin "P$63") (pinfunction "GND_P$63") (pintype "power_in"))
      (node (ref "IC1") (pin "P$64") (pinfunction "GND_P$64") (pintype "power_in"))
      (node (ref "IC1") (pin "P$65") (pinfunction "GND_P$65") (pintype "power_in"))
      (node (ref "IC2") (pin "13") (pinfunction "G_13") (pintype "input"))
      (node (ref "IC2") (pin "8") (pinfunction "GND_8") (pintype "power_in"))
      (node (ref "IC3") (pin "13") (pinfunction "G_13") (pintype "input"))
      (node (ref "IC3") (pin "8") (pinfunction "GND_8") (pintype "power_in"))
      (node (ref "IC4") (pin "2") (pinfunction "DGND_2") (pintype "power_in"))
      (node (ref "IC5") (pin "13") (pinfunction "G_13") (pintype "input"))
      (node (ref "IC5") (pin "8") (pinfunction "GND_8") (pintype "power_in"))
      (node (ref "J5") (pin "GND") (pinfunction "GND_GND") (pintype "bidirectional"))
      (node (ref "J5") (pin "GNDBREAK") (pinfunction "GNDBREAK_GNDBREAK") (pintype "bidirectional"))
      (node (ref "MQ6-R1") (pin "1") (pinfunction "1_1") (pintype "passive"))
      (node (ref "MQ7-R1") (pin "1") (pinfunction "1_1") (pintype "passive"))
      (node (ref "S1") (pin "3") (pinfunction "3_3") (pintype "passive"))
      (node (ref "S1") (pin "4") (pinfunction "4_4") (pintype "passive"))
      (node (ref "SENSOR-DHT") (pin "4") (pinfunction "4_4") (pintype "passive"))
      (node (ref "SENSOR-MQ6") (pin "HB") (pinfunction "HB_HB") (pintype "bidirectional"))
      (node (ref "SENSOR-MQ7") (pin "HB") (pinfunction "HB_HB") (pintype "bidirectional"))
      (node (ref "SIM900-ANT") (pin "GND1") (pinfunction "GND1_GND1") (pintype "power_in"))
      (node (ref "SIM900-ANT") (pin "GND2") (pinfunction "GND2_GND2") (pintype "power_in"))
      (node (ref "SIM900-ANT") (pin "GND3") (pinfunction "GND3_GND3") (pintype "power_in"))
      (node (ref "SIM900-ANT") (pin "GND4") (pinfunction "GND4_GND4") (pintype "power_in"))
      (node (ref "SIM900-C1") (pin "-") (pinfunction "-_-") (pintype "passive"))
      (node (ref "SIM900-C2") (pin "-") (pinfunction "-_-") (pintype "passive"))
      (node (ref "SIM900-C3") (pin "2") (pinfunction "2_2") (pintype "passive"))
      (node (ref "SIM900-C4") (pin "2") (pinfunction "2_2") (pintype "passive"))
      (node (ref "SIM900-C5") (pin "2") (pinfunction "2_2") (pintype "passive"))
      (node (ref "SIM900-R6") (pin "2") (pinfunction "2_2") (pintype "passive"))
      (node (ref "SIM900-R9") (pin "2") (pinfunction "2_2") (pintype "passive"))
      (node (ref "SIM900-T1") (pin "E") (pinfunction "E_E") (pintype "passive"))
      (node (ref "SIM900-T2") (pin "E") (pinfunction "E_E") (pintype "passive"))
      (node (ref "SIM900-T3") (pin "E") (pinfunction "E_E") (pintype "passive"))
      (node (ref "SIM900-T4") (pin "E") (pinfunction "E_E") (pintype "passive"))
      (node (ref "SIM_C1") (pin "1") (pinfunction "1_1") (pintype "passive"))
      (node (ref "SIM_C2") (pin "1") (pinfunction "1_1") (pintype "passive"))
      (node (ref "SIM_HOLDER") (pin "6") (pinfunction "GND_6") (pintype "bidirectional"))
      (node (ref "SR_OUT1") (pin "2") (pinfunction "2_2") (pintype "passive"))
      (node (ref "SR_OUT2") (pin "2") (pinfunction "2_2") (pintype "passive"))
      (node (ref "STM-C1") (pin "1") (pinfunction "1_1") (pintype "passive"))
      (node (ref "STM-C10") (pin "2") (pinfunction "2_2") (pintype "passive"))
      (node (ref "STM-C11") (pin "2") (pinfunction "2_2") (pintype "passive"))
      (node (ref "STM-C12") (pin "2") (pinfunction "2_2") (pintype "passive"))
      (node (ref "STM-C13") (pin "2") (pinfunction "2_2") (pintype "passive"))
      (node (ref "STM-C2") (pin "1") (pinfunction "1_1") (pintype "passive"))
      (node (ref "STM-C3") (pin "1") (pinfunction "1_1") (pintype "passive"))
      (node (ref "STM-C8") (pin "2") (pinfunction "2_2") (pintype "passive"))
      (node (ref "STM-SWD") (pin "3") (pinfunction "3_3") (pintype "passive"))
      (node (ref "STM-USART") (pin "4") (pinfunction "4_4") (pintype "passive"))
      (node (ref "STM_CHIP") (pin "18") (pinfunction "VSS_4_18") (pintype "power_in"))
      (node (ref "STM_CHIP") (pin "31") (pinfunction "VSS_1_31") (pintype "power_in"))
      (node (ref "STM_CHIP") (pin "47") (pinfunction "VSS_2_47") (pintype "power_in"))
      (node (ref "STM_CHIP") (pin "63") (pinfunction "VSS_3_63") (pintype "power_in"))
      (node (ref "SYS-C1") (pin "2") (pinfunction "2_2") (pintype "passive"))
      (node (ref "SYS-C3") (pin "2") (pinfunction "2_2") (pintype "passive"))
      (node (ref "SYS-L1") (pin "2") (pinfunction "2_2") (pintype "passive"))
      (node (ref "U$4") (pin "LCD_GND") (pinfunction "LCD_GND_LCD_GND") (pintype "passive"))
      (node (ref "U2") (pin "14") (pinfunction "AGND_14") (pintype "passive"))
      (node (ref "U2") (pin "16") (pinfunction "AGND_16") (pintype "passive"))
      (node (ref "U2") (pin "19") (pinfunction "AGND_19") (pintype "passive"))
      (node (ref "U2") (pin "29") (pinfunction "GND_29") (pintype "passive"))
      (node (ref "U2") (pin "3") (pinfunction "AGND_3") (pintype "passive"))
      (node (ref "U2") (pin "48") (pinfunction "AGND_48") (pintype "passive"))
      (node (ref "U2") (pin "9") (pinfunction "AGND_9") (pintype "passive"))
      (node (ref "W5500-C1") (pin "2") (pinfunction "2_2") (pintype "passive"))
      (node (ref "W5500-C10") (pin "2") (pinfunction "2_2") (pintype "passive"))
      (node (ref "W5500-C11") (pin "2") (pinfunction "2_2") (pintype "passive"))
      (node (ref "W5500-C12") (pin "-") (pinfunction "-_-") (pintype "passive"))
      (node (ref "W5500-C13") (pin "-") (pinfunction "-_-") (pintype "passive"))
      (node (ref "W5500-C2") (pin "2") (pinfunction "2_2") (pintype "passive"))
      (node (ref "W5500-C3") (pin "2") (pinfunction "2_2") (pintype "passive"))
      (node (ref "W5500-C4") (pin "2") (pinfunction "2_2") (pintype "passive"))
      (node (ref "W5500-C5") (pin "2") (pinfunction "2_2") (pintype "passive"))
      (node (ref "W5500-C6") (pin "2") (pinfunction "2_2") (pintype "passive"))
      (node (ref "W5500-C7") (pin "2") (pinfunction "2_2") (pintype "passive"))
      (node (ref "W5500-C8") (pin "2") (pinfunction "2_2") (pintype "passive"))
      (node (ref "W5500-C9") (pin "2") (pinfunction "2_2") (pintype "passive"))
      (node (ref "W5500-R11") (pin "1") (pinfunction "1_1") (pintype "passive"))
      (node (ref "W5500-R12") (pin "1") (pinfunction "1_1") (pintype "passive"))
      (node (ref "W5500-R4") (pin "2") (pinfunction "2_2") (pintype "passive"))
      (node (ref "W5500-R5") (pin "2") (pinfunction "2_2") (pintype "passive"))
      (node (ref "W5500-R6") (pin "2") (pinfunction "2_2") (pintype "passive"))
      (node (ref "W5500-R7") (pin "2") (pinfunction "2_2") (pintype "passive"))
      (node (ref "W5500-R8") (pin "2") (pinfunction "2_2") (pintype "passive"))
    )
    (net (code "28") (name "DHT_DATA") (class "Default")
      (node (ref "DHT-R1") (pin "2") (pinfunction "2_2") (pintype "passive"))
      (node (ref "SENSOR-DHT") (pin "2") (pinfunction "2_2") (pintype "passive"))
      (node (ref "STM_CHIP") (pin "15") (pinfunction "PA1_15") (pintype "bidirectional"))
    )
    (net (code "29") (name "ESP_GPIO0") (class "Default")
      (node (ref "ESP-GPIO0") (pin "2") (pinfunction "2_2") (pintype "passive"))
      (node (ref "U$5") (pin "GPIO00") (pinfunction "GPIO0_GPIO00") (pintype "bidirectional"))
    )
    (net (code "30") (name "ESP_RX") (class "Default")
      (node (ref "ESP-UART-A") (pin "2") (pinfunction "2_2") (pintype "passive"))
      (node (ref "STM_CHIP") (pin "16") (pinfunction "PA2_16") (pintype "bidirectional"))
      (node (ref "U$5") (pin "RXD") (pinfunction "RXD_RXD") (pintype "bidirectional"))
    )
    (net (code "31") (name "ESP_TX") (class "Default")
      (node (ref "ESP-UART-A") (pin "3") (pinfunction "3_3") (pintype "passive"))
      (node (ref "STM_CHIP") (pin "17") (pinfunction "PA3_17") (pintype "bidirectional"))
      (node (ref "U$5") (pin "TXD") (pinfunction "TXD_TXD") (pintype "bidirectional"))
    )
    (net (code "32") (name "ETH_CS") (class "Default")
      (node (ref "STM_CHIP") (pin "33") (pinfunction "PB12_33") (pintype "bidirectional"))
      (node (ref "U2") (pin "32") (pinfunction "SCS_N_32") (pintype "passive"))
      (node (ref "W5500-R13") (pin "1") (pinfunction "1_1") (pintype "passive"))
    )
    (net (code "33") (name "ETH_MISO") (class "Default")
      (node (ref "STM_CHIP") (pin "35") (pinfunction "PB14_35") (pintype "bidirectional"))
      (node (ref "U2") (pin "34") (pinfunction "MISO_34") (pintype "passive"))
    )
    (net (code "34") (name "ETH_MOSI") (class "Default")
      (node (ref "STM_CHIP") (pin "36") (pinfunction "PB15_36") (pintype "bidirectional"))
      (node (ref "U2") (pin "35") (pinfunction "MOSI_35") (pintype "passive"))
    )
    (net (code "35") (name "ETH_RSTN") (class "Default")
      (node (ref "STM_CHIP") (pin "37") (pinfunction "PC6_37") (pintype "bidirectional"))
      (node (ref "U2") (pin "37") (pinfunction "RST_N_37") (pintype "passive"))
      (node (ref "W5500-R9") (pin "1") (pinfunction "1_1") (pintype "passive"))
    )
    (net (code "36") (name "ETH_SCK") (class "Default")
      (node (ref "STM_CHIP") (pin "34") (pinfunction "PB13_34") (pintype "bidirectional"))
      (node (ref "U2") (pin "33") (pinfunction "SCLK_33") (pintype "passive"))
    )
    (net (code "37") (name "F_CS") (class "Default")
      (node (ref "STM_CHIP") (pin "29") (pinfunction "PB10_29") (pintype "bidirectional"))
      (node (ref "U$4") (pin "F_CS") (pinfunction "F_CS_F_CS") (pintype "passive"))
    )
    (net (code "38") (name "GESP") (class "Default")
      (node (ref "ESP-C1") (pin "2") (pinfunction "2_2") (pintype "passive"))
      (node (ref "ESP-GND") (pin "2") (pinfunction "2_2") (pintype "passive"))
      (node (ref "ESP-GPIO0") (pin "3") (pinfunction "3_3") (pintype "passive"))
      (node (ref "U$5") (pin "GND") (pinfunction "GND_GND") (pintype "bidirectional"))
      (node (ref "U$5") (pin "GPIO15") (pinfunction "GPIO15_GPIO15") (pintype "bidirectional"))
    )
    (net (code "39") (name "GEXT") (class "Default")
      (node (ref "ESP-GND") (pin "3") (pinfunction "3_3") (pintype "passive"))
      (node (ref "ESP-UART-A") (pin "4") (pinfunction "4_4") (pintype "passive"))
    )
    (net (code "40") (name "LCD_CS") (class "Default")
      (node (ref "STM_CHIP") (pin "20") (pinfunction "PA4_20") (pintype "bidirectional"))
      (node (ref "U$4") (pin "LCD_CS") (pinfunction "LCD_CS_LCD_CS") (pintype "passive"))
    )
    (net (code "41") (name "LCD_D{slash}C") (class "Default")
      (node (ref "STM_CHIP") (pin "24") (pinfunction "PC4_24") (pintype "bidirectional"))
      (node (ref "U$4") (pin "LCD_D/C") (pinfunction "LCD_D/C_LCD_D/C") (pintype "passive"))
    )
    (net (code "42") (name "LCD_LED") (class "Default")
      (node (ref "LCD-R1") (pin "1") (pinfunction "1_1") (pintype "passive"))
      (node (ref "U$4") (pin "LCD_LED") (pinfunction "LCD_LED_LCD_LED") (pintype "passive"))
    )
    (net (code "43") (name "LCD_MISO") (class "Default")
      (node (ref "STM_CHIP") (pin "22") (pinfunction "PA6_22") (pintype "bidirectional"))
      (node (ref "U$4") (pin "LCD_MISO") (pinfunction "LCD_MISO_LCD_MISO") (pintype "passive"))
      (node (ref "U$4") (pin "SD_MISO") (pinfunction "SD_MISO_SD_MISO") (pintype "passive"))
    )
    (net (code "44") (name "LCD_MOSI") (class "Default")
      (node (ref "STM_CHIP") (pin "23") (pinfunction "PA7_23") (pintype "bidirectional"))
      (node (ref "U$4") (pin "LCD_MOSI") (pinfunction "LCD_MOSI_LCD_MOSI") (pintype "passive"))
      (node (ref "U$4") (pin "SD_MOSI") (pinfunction "SD_MOSI_SD_MOSI") (pintype "passive"))
    )
    (net (code "45") (name "LCD_RESET") (class "Default")
      (node (ref "STM_CHIP") (pin "25") (pinfunction "PC5_25") (pintype "bidirectional"))
      (node (ref "U$4") (pin "LCD_RESET") (pinfunction "LCD_RESET_LCD_RESET") (pintype "passive"))
    )
    (net (code "46") (name "LCD_SCK") (class "Default")
      (node (ref "STM_CHIP") (pin "21") (pinfunction "PA5_21") (pintype "bidirectional"))
      (node (ref "U$4") (pin "LCD_SCK") (pinfunction "LCD_SCK_LCD_SCK") (pintype "passive"))
      (node (ref "U$4") (pin "SD_SCK") (pinfunction "SD_SCK_SD_SCK") (pintype "passive"))
    )
    (net (code "47") (name "LINKLED") (class "Default")
      (node (ref "ETH-R5") (pin "1") (pinfunction "1_1") (pintype "passive"))
      (node (ref "U2") (pin "25") (pinfunction "LINKLED_25") (pintype "passive"))
    )
    (net (code "48") (name "MQ6_DATA") (class "Default")
      (node (ref "SENSOR-MQ7") (pin "B1") (pinfunction "B1_B1") (pintype "bidirectional"))
      (node (ref "STM_CHIP") (pin "26") (pinfunction "PB0_26") (pintype "bidirectional"))
    )
    (net (code "49") (name "MQ7_DATA") (class "Default")
      (node (ref "SENSOR-MQ6") (pin "B1") (pinfunction "B1_B1") (pintype "bidirectional"))
      (node (ref "STM_CHIP") (pin "27") (pinfunction "PB1_27") (pintype "bidirectional"))
    )
    (net (code "50") (name "Net-(ADE-R1-Pad1)") (class "Default")
      (node (ref "ADE-R1") (pin "1") (pinfunction "1_1") (pintype "passive"))
      (node (ref "VAC_IN1") (pin "PWR") (pinfunction "PWR_PWR") (pintype "bidirectional"))
    )
    (net (code "51") (name "Net-(ADE-R2-Pad1)") (class "Default")
      (node (ref "ADE-R2") (pin "1") (pinfunction "1_1") (pintype "passive"))
      (node (ref "VAC_IN2") (pin "PWR") (pinfunction "PWR_PWR") (pintype "bidirectional"))
    )
    (net (code "52") (name "Net-(ADE-R3-Pad1)") (class "Default")
      (node (ref "ADE-R3") (pin "1") (pinfunction "1_1") (pintype "passive"))
      (node (ref "VAC_IN3") (pin "PWR") (pinfunction "PWR_PWR") (pintype "bidirectional"))
    )
    (net (code "53") (name "Net-(ADE-R7-Pad1)") (class "Default")
      (node (ref "ADE-R7") (pin "1") (pinfunction "1_1") (pintype "passive"))
      (node (ref "VAC_IN1") (pin "GND") (pinfunction "GND_GND") (pintype "bidirectional"))
      (node (ref "VAC_IN1") (pin "GNDBREAK") (pinfunction "GNDBREAK_GNDBREAK") (pintype "bidirectional"))
      (node (ref "VAC_IN2") (pin "GND") (pinfunction "GND_GND") (pintype "bidirectional"))
      (node (ref "VAC_IN2") (pin "GNDBREAK") (pinfunction "GNDBREAK_GNDBREAK") (pintype "bidirectional"))
      (node (ref "VAC_IN3") (pin "GND") (pinfunction "GND_GND") (pintype "bidirectional"))
      (node (ref "VAC_IN3") (pin "GNDBREAK") (pinfunction "GNDBREAK_GNDBREAK") (pintype "bidirectional"))
    )
    (net (code "54") (name "Net-(ADE-R8-Pad2)") (class "Default")
      (node (ref "ADE-R8") (pin "2") (pinfunction "2_2") (pintype "passive"))
      (node (ref "ADE-R9") (pin "1") (pinfunction "1_1") (pintype "passive"))
      (node (ref "CT1") (pin "1") (pinfunction "1_1") (pintype "passive"))
    )
    (net (code "55") (name "Net-(ADE-R10-Pad1)") (class "Default")
      (node (ref "ADE-R10") (pin "1") (pinfunction "1_1") (pintype "passive"))
      (node (ref "ADE-R8") (pin "1") (pinfunction "1_1") (pintype "passive"))
      (node (ref "CT1") (pin "2") (pinfunction "2_2") (pintype "passive"))
      (node (ref "CT1") (pin "5") (pinfunction "5_5") (pintype "passive"))
    )
    (net (code "56") (name "Net-(ADE-R11-Pad1)") (class "Default")
      (node (ref "ADE-R11") (pin "1") (pinfunction "1_1") (pintype "passive"))
      (node (ref "ADE-R13") (pin "1") (pinfunction "1_1") (pintype "passive"))
      (node (ref "CT2") (pin "2") (pinfunction "2_2") (pintype "passive"))
      (node (ref "CT2") (pin "5") (pinfunction "5_5") (pintype "passive"))
    )
    (net (code "57") (name "Net-(ADE-R11-Pad2)") (class "Default")
      (node (ref "ADE-R11") (pin "2") (pinfunction "2_2") (pintype "passive"))
      (node (ref "ADE-R12") (pin "1") (pinfunction "1_1") (pintype "passive"))
      (node (ref "CT2") (pin "1") (pinfunction "1_1") (pintype "passive"))
    )
    (net (code "58") (name "Net-(ADE-R14-Pad1)") (class "Default")
      (node (ref "ADE-R14") (pin "1") (pinfunction "1_1") (pintype "passive"))
      (node (ref "ADE-R16") (pin "1") (pinfunction "1_1") (pintype "passive"))
      (node (ref "CT3") (pin "2") (pinfunction "2_2") (pintype "passive"))
      (node (ref "CT3") (pin "5") (pinfunction "5_5") (pintype "passive"))
    )
    (net (code "59") (name "Net-(ADE-R14-Pad2)") (class "Default")
      (node (ref "ADE-R14") (pin "2") (pinfunction "2_2") (pintype "passive"))
      (node (ref "ADE-R15") (pin "1") (pinfunction "1_1") (pintype "passive"))
      (node (ref "CT3") (pin "1") (pinfunction "1_1") (pintype "passive"))
    )
    (net (code "60") (name "Net-(ETHERNET-LED1_K)") (class "Default")
      (node (ref "ETH-R4") (pin "2") (pinfunction "2_2") (pintype "passive"))
      (node (ref "ETHERNET") (pin "10") (pinfunction "LED1_K_10") (pintype "bidirectional"))
    )
    (net (code "61") (name "Net-(ETHERNET-LED2_K)") (class "Default")
      (node (ref "ETH-R5") (pin "2") (pinfunction "2_2") (pintype "passive"))
      (node (ref "ETHERNET") (pin "11") (pinfunction "LED2_K_11") (pintype "bidirectional"))
    )
    (net (code "62") (name "Net-(ETHERNET-RCT)") (class "Default")
      (node (ref "ETH-C3") (pin "2") (pinfunction "2_2") (pintype "passive"))
      (node (ref "ETH-R6") (pin "1") (pinfunction "1_1") (pintype "passive"))
      (node (ref "ETH-R7") (pin "2") (pinfunction "2_2") (pintype "passive"))
      (node (ref "ETHERNET") (pin "6") (pinfunction "RCT_6") (pintype "bidirectional"))
    )
    (net (code "63") (name "Net-(ETHERNET-RX+)") (class "Default")
      (node (ref "ETH-C2") (pin "1") (pinfunction "1_1") (pintype "passive"))
      (node (ref "ETHERNET") (pin "7") (pinfunction "RX+_7") (pintype "bidirectional"))
    )
    (net (code "64") (name "Net-(ETHERNET-RX-)") (class "Default")
      (node (ref "ETH-C4") (pin "1") (pinfunction "1_1") (pintype "passive"))
      (node (ref "ETHERNET") (pin "8") (pinfunction "RX-_8") (pintype "bidirectional"))
    )
    (net (code "65") (name "Net-(ETHERNET-TCT)") (class "Default")
      (node (ref "ETH-C1") (pin "2") (pinfunction "2_2") (pintype "passive"))
      (node (ref "ETH-R3") (pin "1") (pinfunction "1_1") (pintype "passive"))
      (node (ref "ETHERNET") (pin "3") (pinfunction "TCT_3") (pintype "bidirectional"))
    )
    (net (code "66") (name "Net-(IC1-RF_ANT)") (class "Default")
      (node (ref "IC1") (pin "P$60") (pinfunction "RF_ANT_P$60") (pintype "bidirectional"))
      (node (ref "SIM900-ANT") (pin "ANTENNA") (pinfunction "ANT_ANTENNA") (pintype "bidirectional"))
    )
    (net (code "67") (name "Net-(IC1-SIM_CLK)") (class "Default")
      (node (ref "IC1") (pin "P$32") (pinfunction "SIM_CLK_P$32") (pintype "bidirectional"))
      (node (ref "SIM900-R2") (pin "1") (pinfunction "1_1") (pintype "passive"))
    )
    (net (code "68") (name "Net-(IC1-SIM_DATA)") (class "Default")
      (node (ref "IC1") (pin "P$31") (pinfunction "SIM_DATA_P$31") (pintype "bidirectional"))
      (node (ref "SIM900-R3") (pin "1") (pinfunction "1_1") (pintype "passive"))
    )
    (net (code "69") (name "Net-(IC1-SIM_RST)") (class "Default")
      (node (ref "IC1") (pin "P$33") (pinfunction "SIM_RST_P$33") (pintype "bidirectional"))
      (node (ref "SIM900-R1") (pin "1") (pinfunction "1_1") (pintype "passive"))
    )
    (net (code "70") (name "Net-(IC1-VRTC)") (class "Default")
      (node (ref "IC1") (pin "P$26") (pinfunction "VRTC_P$26") (pintype "power_in"))
      (node (ref "SIM900-C3") (pin "1") (pinfunction "1_1") (pintype "passive"))
    )
    (net (code "71") (name "Net-(IC4A-CLKIN)") (class "Default")
      (node (ref "ADE-C3") (pin "1") (pinfunction "1_1") (pintype "passive"))
      (node (ref "ADE-XTAL") (pin "1") (pinfunction "1_1") (pintype "passive"))
      (node (ref "IC4") (pin "19") (pinfunction "CLKIN_19") (pintype "input"))
    )
    (net (code "72") (name "Net-(IC4A-CLKOUT)") (class "Default")
      (node (ref "ADE-C4") (pin "1") (pinfunction "1_1") (pintype "passive"))
      (node (ref "ADE-XTAL") (pin "2") (pinfunction "2_2") (pintype "passive"))
      (node (ref "IC4") (pin "20") (pinfunction "CLKOUT_20") (pintype "output"))
    )
    (net (code "73") (name "Net-(IC4C-IN)") (class "Default")
      (node (ref "ADE-C12") (pin "1") (pinfunction "1_1") (pintype "passive"))
      (node (ref "ADE-R10") (pin "2") (pinfunction "2_2") (pintype "passive"))
      (node (ref "IC4") (pin "6") (pinfunction "IN_6") (pintype "input"))
    )
    (net (code "74") (name "Net-(IC4C-IP)") (class "Default")
      (node (ref "ADE-C11") (pin "1") (pinfunction "1_1") (pintype "passive"))
      (node (ref "ADE-R9") (pin "2") (pinfunction "2_2") (pintype "passive"))
      (node (ref "IC4") (pin "5") (pinfunction "IP_5") (pintype "input"))
    )
    (net (code "75") (name "Net-(IC4D-IN)") (class "Default")
      (node (ref "ADE-C14") (pin "1") (pinfunction "1_1") (pintype "passive"))
      (node (ref "ADE-R13") (pin "2") (pinfunction "2_2") (pintype "passive"))
      (node (ref "IC4") (pin "8") (pinfunction "IN_8") (pintype "input"))
    )
    (net (code "76") (name "Net-(IC4D-IP)") (class "Default")
      (node (ref "ADE-C13") (pin "1") (pinfunction "1_1") (pintype "passive"))
      (node (ref "ADE-R12") (pin "2") (pinfunction "2_2") (pintype "passive"))
      (node (ref "IC4") (pin "7") (pinfunction "IP_7") (pintype "input"))
    )
    (net (code "77") (name "Net-(IC4E-IN)") (class "Default")
      (node (ref "ADE-C16") (pin "1") (pinfunction "1_1") (pintype "passive"))
      (node (ref "ADE-R16") (pin "2") (pinfunction "2_2") (pintype "passive"))
      (node (ref "IC4") (pin "10") (pinfunction "IN_10") (pintype "input"))
    )
    (net (code "78") (name "Net-(IC4E-IP)") (class "Default")
      (node (ref "ADE-C15") (pin "1") (pinfunction "1_1") (pintype "passive"))
      (node (ref "ADE-R15") (pin "2") (pinfunction "2_2") (pintype "passive"))
      (node (ref "IC4") (pin "9") (pinfunction "IP_9") (pintype "input"))
    )
    (net (code "79") (name "Net-(IC4F-REF)") (class "Default")
      (node (ref "ADE-C1") (pin "1") (pinfunction "1_1") (pintype "passive"))
      (node (ref "ADE-C2") (pin "1") (pinfunction "1_1") (pintype "passive"))
      (node (ref "IC4") (pin "12") (pinfunction "REF_12") (pintype "bidirectional"))
    )
    (net (code "80") (name "Net-(IC4G-VAP)") (class "Default")
      (node (ref "ADE-C7") (pin "1") (pinfunction "1_1") (pintype "passive"))
      (node (ref "ADE-R1") (pin "2") (pinfunction "2_2") (pintype "passive"))
      (node (ref "ADE-R4") (pin "2") (pinfunction "2_2") (pintype "passive"))
      (node (ref "IC4") (pin "16") (pinfunction "VAP_16") (pintype "input"))
    )
    (net (code "81") (name "Net-(IC4G-VBP)") (class "Default")
      (node (ref "ADE-C8") (pin "1") (pinfunction "1_1") (pintype "passive"))
      (node (ref "ADE-R2") (pin "2") (pinfunction "2_2") (pintype "passive"))
      (node (ref "ADE-R5") (pin "2") (pinfunction "2_2") (pintype "passive"))
      (node (ref "IC4") (pin "15") (pinfunction "VBP_15") (pintype "input"))
    )
    (net (code "82") (name "Net-(IC4G-VCP)") (class "Default")
      (node (ref "ADE-C9") (pin "1") (pinfunction "1_1") (pintype "passive"))
      (node (ref "ADE-R3") (pin "2") (pinfunction "2_2") (pintype "passive"))
      (node (ref "ADE-R6") (pin "2") (pinfunction "2_2") (pintype "passive"))
      (node (ref "IC4") (pin "14") (pinfunction "VCP_14") (pintype "input"))
    )
    (net (code "83") (name "Net-(IC4G-VN)") (class "Default")
      (node (ref "ADE-C10") (pin "1") (pinfunction "1_1") (pintype "passive"))
      (node (ref "ADE-R7") (pin "2") (pinfunction "2_2") (pintype "passive"))
      (node (ref "IC4") (pin "13") (pinfunction "VN_13") (pintype "input"))
    )
    (net (code "84") (name "Net-(MQ6-R1-Pad2)") (class "Default")
      (node (ref "MQ6-R1") (pin "2") (pinfunction "2_2") (pintype "passive"))
      (node (ref "SENSOR-MQ6") (pin "B2") (pinfunction "B2_B2") (pintype "bidirectional"))
    )
    (net (code "85") (name "Net-(MQ7-R1-Pad2)") (class "Default")
      (node (ref "MQ7-R1") (pin "2") (pinfunction "2_2") (pintype "passive"))
      (node (ref "SENSOR-MQ7") (pin "B2") (pinfunction "B2_B2") (pintype "bidirectional"))
    )
    (net (code "86") (name "Net-(OK1A-A)") (class "Default")
      (node (ref "OK1") (pin "1") (pinfunction "A_1") (pintype "passive"))
      (node (ref "R_CH3") (pin "2") (pinfunction "2_2") (pintype "passive"))
    )
    (net (code "87") (name "Net-(OK1B-A)") (class "Default")
      (node (ref "OK1") (pin "3") (pinfunction "A_3") (pintype "passive"))
      (node (ref "R_CH4") (pin "2") (pinfunction "2_2") (pintype "passive"))
    )
    (net (code "88") (name "Net-(OK2A-A)") (class "Default")
      (node (ref "OK2") (pin "1") (pinfunction "A_1") (pintype "passive"))
      (node (ref "R_CH1") (pin "2") (pinfunction "2_2") (pintype "passive"))
    )
    (net (code "89") (name "Net-(OK2B-A)") (class "Default")
      (node (ref "OK2") (pin "3") (pinfunction "A_3") (pintype "passive"))
      (node (ref "R_CH2") (pin "2") (pinfunction "2_2") (pintype "passive"))
    )
    (net (code "90") (name "Net-(SIM900-LED1-PadA)") (class "Default")
      (node (ref "SIM900-LED1") (pin "A") (pinfunction "A_A") (pintype "passive"))
      (node (ref "SIM900-R4") (pin "1") (pinfunction "1_1") (pintype "passive"))
    )
    (net (code "91") (name "Net-(SIM900-LED1-PadC)") (class "Default")
      (node (ref "SIM900-LED1") (pin "C") (pinfunction "C_C") (pintype "passive"))
      (node (ref "SIM900-T1") (pin "C") (pinfunction "C_C") (pintype "passive"))
    )
    (net (code "92") (name "Net-(SIM900-LED2-PadA)") (class "Default")
      (node (ref "SIM900-LED2") (pin "A") (pinfunction "A_A") (pintype "passive"))
      (node (ref "SIM900-R7") (pin "1") (pinfunction "1_1") (pintype "passive"))
    )
    (net (code "93") (name "Net-(SIM900-LED2-PadC)") (class "Default")
      (node (ref "SIM900-LED2") (pin "C") (pinfunction "C_C") (pintype "passive"))
      (node (ref "SIM900-T2") (pin "C") (pinfunction "C_C") (pintype "passive"))
    )
    (net (code "94") (name "Net-(SIM900-R5-Pad1)") (class "Default")
      (node (ref "SIM900-R5") (pin "1") (pinfunction "1_1") (pintype "passive"))
      (node (ref "SIM900-R6") (pin "1") (pinfunction "1_1") (pintype "passive"))
      (node (ref "SIM900-T1") (pin "B") (pinfunction "B_B") (pintype "passive"))
    )
    (net (code "95") (name "Net-(SIM900-R8-Pad1)") (class "Default")
      (node (ref "SIM900-R8") (pin "1") (pinfunction "1_1") (pintype "passive"))
      (node (ref "SIM900-R9") (pin "1") (pinfunction "1_1") (pintype "passive"))
      (node (ref "SIM900-T2") (pin "B") (pinfunction "B_B") (pintype "passive"))
    )
    (net (code "96") (name "Net-(SIM900-R10-Pad2)") (class "Default")
      (node (ref "SIM900-R10") (pin "2") (pinfunction "2_2") (pintype "passive"))
      (node (ref "SIM900-T3") (pin "B") (pinfunction "B_B") (pintype "passive"))
    )
    (net (code "97") (name "Net-(SIM900-R11-Pad2)") (class "Default")
      (node (ref "SIM900-R11") (pin "2") (pinfunction "2_2") (pintype "passive"))
      (node (ref "SIM900-T4") (pin "B") (pinfunction "B_B") (pintype "passive"))
    )
    (net (code "98") (name "Net-(STM_CHIP-PC14-OSC32_IN)") (class "Default")
      (node (ref "STM-C2") (pin "2") (pinfunction "2_2") (pintype "passive"))
      (node (ref "STM-XTAL") (pin "2") (pinfunction "2_2") (pintype "passive"))
      (node (ref "STM_CHIP") (pin "3") (pinfunction "PC14-OSC32_IN_3") (pintype "bidirectional"))
    )
    (net (code "99") (name "Net-(STM_CHIP-PC15-OSC32_OUT)") (class "Default")
      (node (ref "STM-C3") (pin "2") (pinfunction "2_2") (pintype "passive"))
      (node (ref "STM-XTAL") (pin "1") (pinfunction "1_1") (pintype "passive"))
      (node (ref "STM_CHIP") (pin "4") (pinfunction "PC15-OSC32_OUT_4") (pintype "bidirectional"))
    )
    (net (code "100") (name "Net-(U2-1V2O)") (class "Default")
      (node (ref "U2") (pin "22") (pinfunction "1V2O_22") (pintype "passive"))
      (node (ref "W5500-C4") (pin "1") (pinfunction "1_1") (pintype "passive"))
    )
    (net (code "101") (name "Net-(U2-EXRES1)") (class "Default")
      (node (ref "U2") (pin "10") (pinfunction "EXRES1_10") (pintype "passive"))
      (node (ref "W5500-R12") (pin "2") (pinfunction "2_2") (pintype "passive"))
    )
    (net (code "102") (name "Net-(U2-PMODE0)") (class "Default")
      (node (ref "U2") (pin "45") (pinfunction "PMODE0_45") (pintype "passive"))
      (node (ref "W5500-R3") (pin "2") (pinfunction "2_2") (pintype "passive"))
    )
    (net (code "103") (name "Net-(U2-PMODE1)") (class "Default")
      (node (ref "U2") (pin "44") (pinfunction "PMODE1_44") (pintype "passive"))
      (node (ref "W5500-R2") (pin "2") (pinfunction "2_2") (pintype "passive"))
    )
    (net (code "104") (name "Net-(U2-PMODE2)") (class "Default")
      (node (ref "U2") (pin "43") (pinfunction "PMODE2_43") (pintype "passive"))
      (node (ref "W5500-R1") (pin "2") (pinfunction "2_2") (pintype "passive"))
    )
    (net (code "105") (name "Net-(U2-RSVD-Pad23)") (class "Default")
      (node (ref "U2") (pin "23") (pinfunction "RSVD_23") (pintype "passive"))
      (node (ref "W5500-R11") (pin "2") (pinfunction "2_2") (pintype "passive"))
    )
    (net (code "106") (name "Net-(U2-RSVD-Pad38)") (class "Default")
      (node (ref "U2") (pin "38") (pinfunction "RSVD_38") (pintype "passive"))
      (node (ref "W5500-R8") (pin "1") (pinfunction "1_1") (pintype "passive"))
    )
    (net (code "107") (name "Net-(U2-RSVD-Pad39)") (class "Default")
      (node (ref "U2") (pin "39") (pinfunction "RSVD_39") (pintype "passive"))
      (node (ref "W5500-R7") (pin "1") (pinfunction "1_1") (pintype "passive"))
    )
    (net (code "108") (name "Net-(U2-RSVD-Pad40)") (class "Default")
      (node (ref "U2") (pin "40") (pinfunction "RSVD_40") (pintype "passive"))
      (node (ref "W5500-R6") (pin "1") (pinfunction "1_1") (pintype "passive"))
    )
    (net (code "109") (name "Net-(U2-RSVD-Pad41)") (class "Default")
      (node (ref "U2") (pin "41") (pinfunction "RSVD_41") (pintype "passive"))
      (node (ref "W5500-R5") (pin "1") (pinfunction "1_1") (pintype "passive"))
    )
    (net (code "110") (name "Net-(U2-RSVD-Pad42)") (class "Default")
      (node (ref "U2") (pin "42") (pinfunction "RSVD_42") (pintype "passive"))
      (node (ref "W5500-R4") (pin "1") (pinfunction "1_1") (pintype "passive"))
    )
    (net (code "111") (name "Net-(U2-TOCAP)") (class "Default")
      (node (ref "U2") (pin "20") (pinfunction "TOCAP_20") (pintype "passive"))
      (node (ref "W5500-C3") (pin "1") (pinfunction "1_1") (pintype "passive"))
    )
    (net (code "112") (name "Net-(U2-XI{slash}CLKIN)") (class "Default")
      (node (ref "U$3") (pin "P$1") (pinfunction "P$1_P$1") (pintype "bidirectional"))
      (node (ref "U2") (pin "30") (pinfunction "XI/CLKIN_30") (pintype "passive"))
      (node (ref "W5500-C1") (pin "1") (pinfunction "1_1") (pintype "passive"))
      (node (ref "W5500-R10") (pin "1") (pinfunction "1_1") (pintype "passive"))
      (node (ref "W5500-XTAL") (pin "1") (pinfunction "1_1") (pintype "passive"))
    )
    (net (code "113") (name "Net-(U2-XO)") (class "Default")
      (node (ref "U$3") (pin "P$2") (pinfunction "P$2_P$2") (pintype "bidirectional"))
      (node (ref "U2") (pin "31") (pinfunction "XO_31") (pintype "passive"))
      (node (ref "W5500-C2") (pin "1") (pinfunction "1_1") (pintype "passive"))
      (node (ref "W5500-R10") (pin "2") (pinfunction "2_2") (pintype "passive"))
      (node (ref "W5500-XTAL") (pin "2") (pinfunction "2_2") (pintype "passive"))
    )
    (net (code "114") (name "Q1") (class "Default")
      (node (ref "IC2") (pin "15") (pinfunction "QA_15") (pintype "tri_state"))
      (node (ref "SR_OUT1") (pin "3") (pinfunction "3_3") (pintype "passive"))
    )
    (net (code "115") (name "Q2") (class "Default")
      (node (ref "IC2") (pin "1") (pinfunction "QB_1") (pintype "tri_state"))
      (node (ref "SR_OUT1") (pin "4") (pinfunction "4_4") (pintype "passive"))
    )
    (net (code "116") (name "Q3") (class "Default")
      (node (ref "IC2") (pin "2") (pinfunction "QC_2") (pintype "tri_state"))
      (node (ref "SR_OUT1") (pin "5") (pinfunction "5_5") (pintype "passive"))
    )
    (net (code "117") (name "Q4") (class "Default")
      (node (ref "IC2") (pin "3") (pinfunction "QD_3") (pintype "tri_state"))
      (node (ref "SR_OUT1") (pin "6") (pinfunction "6_6") (pintype "passive"))
    )
    (net (code "118") (name "Q5") (class "Default")
      (node (ref "IC2") (pin "4") (pinfunction "QE_4") (pintype "tri_state"))
      (node (ref "SR_OUT1") (pin "7") (pinfunction "7_7") (pintype "passive"))
    )
    (net (code "119") (name "Q6") (class "Default")
      (node (ref "IC2") (pin "5") (pinfunction "QF_5") (pintype "tri_state"))
      (node (ref "SR_OUT1") (pin "8") (pinfunction "8_8") (pintype "passive"))
    )
    (net (code "120") (name "Q7") (class "Default")
      (node (ref "IC2") (pin "6") (pinfunction "QG_6") (pintype "tri_state"))
      (node (ref "SR_OUT1") (pin "9") (pinfunction "9_9") (pintype "passive"))
    )
    (net (code "121") (name "Q8") (class "Default")
      (node (ref "IC2") (pin "7") (pinfunction "QH_7") (pintype "tri_state"))
      (node (ref "SR_OUT1") (pin "10") (pinfunction "10_10") (pintype "passive"))
    )
    (net (code "122") (name "Q9") (class "Default")
      (node (ref "IC3") (pin "15") (pinfunction "QA_15") (pintype "tri_state"))
      (node (ref "SR_OUT2") (pin "3") (pinfunction "3_3") (pintype "passive"))
    )
    (net (code "123") (name "Q10") (class "Default")
      (node (ref "IC3") (pin "1") (pinfunction "QB_1") (pintype "tri_state"))
      (node (ref "SR_OUT2") (pin "4") (pinfunction "4_4") (pintype "passive"))
    )
    (net (code "124") (name "Q11") (class "Default")
      (node (ref "IC3") (pin "2") (pinfunction "QC_2") (pintype "tri_state"))
      (node (ref "SR_OUT2") (pin "5") (pinfunction "5_5") (pintype "passive"))
    )
    (net (code "125") (name "Q12") (class "Default")
      (node (ref "IC3") (pin "3") (pinfunction "QD_3") (pintype "tri_state"))
      (node (ref "SR_OUT2") (pin "6") (pinfunction "6_6") (pintype "passive"))
    )
    (net (code "126") (name "Q13") (class "Default")
      (node (ref "IC3") (pin "4") (pinfunction "QE_4") (pintype "tri_state"))
      (node (ref "SR_OUT2") (pin "7") (pinfunction "7_7") (pintype "passive"))
    )
    (net (code "127") (name "Q14") (class "Default")
      (node (ref "IC3") (pin "5") (pinfunction "QF_5") (pintype "tri_state"))
      (node (ref "SR_OUT2") (pin "8") (pinfunction "8_8") (pintype "passive"))
    )
    (net (code "128") (name "Q15") (class "Default")
      (node (ref "IC3") (pin "6") (pinfunction "QG_6") (pintype "tri_state"))
      (node (ref "SR_OUT2") (pin "9") (pinfunction "9_9") (pintype "passive"))
    )
    (net (code "129") (name "Q16") (class "Default")
      (node (ref "IC3") (pin "7") (pinfunction "QH_7") (pintype "tri_state"))
      (node (ref "SR_OUT2") (pin "10") (pinfunction "10_10") (pintype "passive"))
    )
    (net (code "130") (name "QS") (class "Default")
      (node (ref "IC2") (pin "9") (pinfunction "QH*_9") (pintype "tri_state"))
      (node (ref "IC3") (pin "14") (pinfunction "SER_14") (pintype "input"))
    )
    (net (code "131") (name "QS2") (class "Default")
      (node (ref "IC3") (pin "9") (pinfunction "QH*_9") (pintype "tri_state"))
      (node (ref "IC5") (pin "14") (pinfunction "SER_14") (pintype "input"))
    )
    (net (code "132") (name "RXN") (class "Default")
      (node (ref "ETH-C4") (pin "2") (pinfunction "2_2") (pintype "passive"))
      (node (ref "ETH-R7") (pin "1") (pinfunction "1_1") (pintype "passive"))
      (node (ref "U2") (pin "5") (pinfunction "RXN_5") (pintype "passive"))
    )
    (net (code "133") (name "RXP") (class "Default")
      (node (ref "ETH-C2") (pin "2") (pinfunction "2_2") (pintype "passive"))
      (node (ref "ETH-R6") (pin "2") (pinfunction "2_2") (pintype "passive"))
      (node (ref "U2") (pin "6") (pinfunction "RXP_6") (pintype "passive"))
    )
    (net (code "134") (name "SD_CS") (class "Default")
      (node (ref "STM_CHIP") (pin "53") (pinfunction "PC12_53") (pintype "bidirectional"))
      (node (ref "U$4") (pin "SD_CS") (pinfunction "SD_CS_SD_CS") (pintype "passive"))
    )
    (net (code "135") (name "SERIAL_RX") (class "Default")
      (node (ref "STM-USART") (pin "3") (pinfunction "3_3") (pintype "passive"))
      (node (ref "STM_CHIP") (pin "43") (pinfunction "PA10_43") (pintype "bidirectional"))
    )
    (net (code "136") (name "SERIAL_TX") (class "Default")
      (node (ref "STM-USART") (pin "2") (pinfunction "2_2") (pintype "passive"))
      (node (ref "STM_CHIP") (pin "42") (pinfunction "PA9_42") (pintype "bidirectional"))
    )
    (net (code "137") (name "SIM900_PWRKEY") (class "Default")
      (node (ref "IC1") (pin "P$1") (pinfunction "PWRKEY_P$1") (pintype "power_in"))
      (node (ref "SIM900-T3") (pin "C") (pinfunction "C_C") (pintype "passive"))
    )
    (net (code "138") (name "SIM900_RESET") (class "Default")
      (node (ref "IC1") (pin "P$16") (pinfunction "NRESET_P$16") (pintype "bidirectional"))
      (node (ref "SIM900-T4") (pin "C") (pinfunction "C_C") (pintype "passive"))
    )
    (net (code "139") (name "SIM_NETLIGHT") (class "Default")
      (node (ref "IC1") (pin "P$52") (pinfunction "NETLIGHT_P$52") (pintype "bidirectional"))
      (node (ref "SIM900-R8") (pin "2") (pinfunction "2_2") (pintype "passive"))
    )
    (net (code "140") (name "SIM_PWRKEY") (class "Default")
      (node (ref "SIM900-R10") (pin "1") (pinfunction "1_1") (pintype "passive"))
      (node (ref "STM_CHIP") (pin "40") (pinfunction "PC9_40") (pintype "bidirectional"))
    )
    (net (code "141") (name "SIM_RESET") (class "Default")
      (node (ref "SIM900-R11") (pin "1") (pinfunction "1_1") (pintype "passive"))
      (node (ref "STM_CHIP") (pin "50") (pinfunction "PA15_50") (pintype "bidirectional"))
    )
    (net (code "142") (name "SIM_RX") (class "Default")
      (node (ref "IC1") (pin "P$10") (pinfunction "RXD_P$10") (pintype "input"))
      (node (ref "STM_CHIP") (pin "51") (pinfunction "PC10_51") (pintype "bidirectional"))
    )
    (net (code "143") (name "SIM_STATUS") (class "Default")
      (node (ref "IC1") (pin "P$66") (pinfunction "STATUS_P$66") (pintype "bidirectional"))
      (node (ref "SIM900-R5") (pin "2") (pinfunction "2_2") (pintype "passive"))
    )
    (net (code "144") (name "SIM_TX") (class "Default")
      (node (ref "IC1") (pin "P$9") (pinfunction "TXD_P$9") (pintype "output"))
      (node (ref "STM_CHIP") (pin "52") (pinfunction "PC11_52") (pintype "bidirectional"))
    )
    (net (code "145") (name "SR_DS") (class "Default")
      (node (ref "IC2") (pin "14") (pinfunction "SER_14") (pintype "input"))
      (node (ref "STM_CHIP") (pin "8") (pinfunction "PC0_8") (pintype "bidirectional"))
    )
    (net (code "146") (name "SR_RST") (class "Default")
      (node (ref "IC2") (pin "10") (pinfunction "SCL_10") (pintype "input"))
      (node (ref "IC3") (pin "10") (pinfunction "SCL_10") (pintype "input"))
      (node (ref "IC5") (pin "10") (pinfunction "SCL_10") (pintype "input"))
      (node (ref "STM_CHIP") (pin "11") (pinfunction "PC3_11") (pintype "bidirectional"))
    )
    (net (code "147") (name "SR_SHCP") (class "Default")
      (node (ref "IC2") (pin "11") (pinfunction "SCK_11") (pintype "input"))
      (node (ref "IC3") (pin "11") (pinfunction "SCK_11") (pintype "input"))
      (node (ref "IC5") (pin "11") (pinfunction "SCK_11") (pintype "input"))
      (node (ref "STM_CHIP") (pin "10") (pinfunction "PC2_10") (pintype "bidirectional"))
    )
    (net (code "148") (name "SR_STCP") (class "Default")
      (node (ref "IC2") (pin "12") (pinfunction "RCK_12") (pintype "input"))
      (node (ref "IC3") (pin "12") (pinfunction "RCK_12") (pintype "input"))
      (node (ref "IC5") (pin "12") (pinfunction "RCK_12") (pintype "input"))
      (node (ref "STM_CHIP") (pin "9") (pinfunction "PC1_9") (pintype "bidirectional"))
    )
    (net (code "149") (name "SWD_NRST") (class "Default")
      (node (ref "S1") (pin "1") (pinfunction "1_1") (pintype "passive"))
      (node (ref "S1") (pin "2") (pinfunction "2_2") (pintype "passive"))
      (node (ref "STM-C8") (pin "1") (pinfunction "1_1") (pintype "passive"))
      (node (ref "STM_CHIP") (pin "7") (pinfunction "NRST_7") (pintype "bidirectional"))
    )
    (net (code "150") (name "SWD_TCK") (class "Default")
      (node (ref "STM-SWD") (pin "2") (pinfunction "2_2") (pintype "passive"))
      (node (ref "STM_CHIP") (pin "49") (pinfunction "PA14_49") (pintype "bidirectional"))
    )
    (net (code "151") (name "SWD_TMS") (class "Default")
      (node (ref "STM-SWD") (pin "4") (pinfunction "4_4") (pintype "passive"))
      (node (ref "STM_CHIP") (pin "46") (pinfunction "PA13_46") (pintype "bidirectional"))
    )
    (net (code "152") (name "TXN") (class "Default")
      (node (ref "ETH-R2") (pin "1") (pinfunction "1_1") (pintype "passive"))
      (node (ref "ETHERNET") (pin "2") (pinfunction "TX-_2") (pintype "bidirectional"))
      (node (ref "U2") (pin "1") (pinfunction "TXN_1") (pintype "passive"))
    )
    (net (code "153") (name "TXP") (class "Default")
      (node (ref "ETH-R1") (pin "1") (pinfunction "1_1") (pintype "passive"))
      (node (ref "ETHERNET") (pin "1") (pinfunction "TX+_1") (pintype "bidirectional"))
      (node (ref "U2") (pin "2") (pinfunction "TXP_2") (pintype "passive"))
    )
    (net (code "154") (name "USIM_CLK") (class "Default")
      (node (ref "SIM900-R2") (pin "2") (pinfunction "2_2") (pintype "passive"))
      (node (ref "SIM_HOLDER") (pin "3") (pinfunction "CLK_3") (pintype "bidirectional"))
    )
    (net (code "155") (name "USIM_DATA") (class "Default")
      (node (ref "SIM900-R3") (pin "2") (pinfunction "2_2") (pintype "passive"))
      (node (ref "SIM_HOLDER") (pin "4") (pinfunction "I/O_4") (pintype "bidirectional"))
    )
    (net (code "156") (name "USIM_RESET") (class "Default")
      (node (ref "SIM900-R1") (pin "2") (pinfunction "2_2") (pintype "passive"))
      (node (ref "SIM_HOLDER") (pin "2") (pinfunction "RST_2") (pintype "bidirectional"))
    )
    (net (code "157") (name "USIM_VCC") (class "Default")
      (node (ref "IC1") (pin "P$30") (pinfunction "SIM_VDD_P$30") (pintype "power_in"))
      (node (ref "SIM900-C4") (pin "1") (pinfunction "1_1") (pintype "passive"))
      (node (ref "SIM900-C5") (pin "1") (pinfunction "1_1") (pintype "passive"))
      (node (ref "SIM_C1") (pin "2") (pinfunction "2_2") (pintype "passive"))
      (node (ref "SIM_C2") (pin "2") (pinfunction "2_2") (pintype "passive"))
      (node (ref "SIM_HOLDER") (pin "1") (pinfunction "VCC_1") (pintype "bidirectional"))
    )
    (net (code "158") (name "VBAT") (class "Default")
      (node (ref "BAT1") (pin "1") (pinfunction "+_1") (pintype "power_in"))
      (node (ref "STM_CHIP") (pin "1") (pinfunction "VLCD_1") (pintype "power_in"))
    )
    (net (code "159") (name "VCC") (class "Default")
      (node (ref "ETH-R1") (pin "2") (pinfunction "2_2") (pintype "passive"))
      (node (ref "ETH-R2") (pin "2") (pinfunction "2_2") (pintype "passive"))
      (node (ref "ETH-R3") (pin "2") (pinfunction "2_2") (pintype "passive"))
      (node (ref "STM-C9") (pin "1") (pinfunction "1_1") (pintype "passive"))
      (node (ref "STM-L1") (pin "2") (pinfunction "2_2") (pintype "passive"))
      (node (ref "STM_CHIP") (pin "13") (pinfunction "VDDA_13") (pintype "power_in"))
      (node (ref "SYS-C4") (pin "1") (pinfunction "1_1") (pintype "passive"))
      (node (ref "SYS-R2") (pin "2") (pinfunction "2_2") (pintype "passive"))
      (node (ref "U2") (pin "11") (pinfunction "AVDD_11") (pintype "passive"))
      (node (ref "U2") (pin "15") (pinfunction "AVDD_15") (pintype "passive"))
      (node (ref "U2") (pin "17") (pinfunction "AVDD_17") (pintype "passive"))
      (node (ref "U2") (pin "21") (pinfunction "AVDD_21") (pintype "passive"))
      (node (ref "U2") (pin "4") (pinfunction "AVDD_4") (pintype "passive"))
      (node (ref "U2") (pin "8") (pinfunction "AVDD_8") (pintype "passive"))
      (node (ref "W5500-C10") (pin "1") (pinfunction "1_1") (pintype "passive"))
      (node (ref "W5500-C11") (pin "1") (pinfunction "1_1") (pintype "passive"))
      (node (ref "W5500-C12") (pin "+") (pinfunction "+_+") (pintype "passive"))
      (node (ref "W5500-C6") (pin "1") (pinfunction "1_1") (pintype "passive"))
      (node (ref "W5500-C7") (pin "1") (pinfunction "1_1") (pintype "passive"))
      (node (ref "W5500-C8") (pin "1") (pinfunction "1_1") (pintype "passive"))
      (node (ref "W5500-C9") (pin "1") (pinfunction "1_1") (pintype "passive"))
    )
    (net (code "160") (name "VDD") (class "Default")
      (node (ref "DHT-R1") (pin "1") (pinfunction "1_1") (pintype "passive"))
      (node (ref "ESP-VDD") (pin "1") (pinfunction "1_1") (pintype "passive"))
      (node (ref "ETHERNET") (pin "12") (pinfunction "LED2_A_12") (pintype "bidirectional"))
      (node (ref "ETHERNET") (pin "9") (pinfunction "LED1_A_9") (pintype "bidirectional"))
      (node (ref "IC1") (pin "P$55") (pinfunction "VBAT1_P$55") (pintype "power_in"))
      (node (ref "IC1") (pin "P$56") (pinfunction "VBAT2_P$56") (pintype "power_in"))
      (node (ref "IC1") (pin "P$57") (pinfunction "VBAT3_P$57") (pintype "power_in"))
      (node (ref "IC2") (pin "16") (pinfunction "VCC_16") (pintype "power_in"))
      (node (ref "IC3") (pin "16") (pinfunction "VCC_16") (pintype "power_in"))
      (node (ref "IC5") (pin "16") (pinfunction "VCC_16") (pintype "power_in"))
      (node (ref "LCD-R1") (pin "2") (pinfunction "2_2") (pintype "passive"))
      (node (ref "PWR-SWT") (pin "1") (pinfunction "1_1") (pintype "passive"))
      (node (ref "SENSOR-DHT") (pin "1") (pinfunction "1_1") (pintype "passive"))
      (node (ref "SIM900-C1") (pin "+") (pinfunction "+_+") (pintype "passive"))
      (node (ref "SIM900-C2") (pin "+") (pinfunction "+_+") (pintype "passive"))
      (node (ref "SIM900-R4") (pin "2") (pinfunction "2_2") (pintype "passive"))
      (node (ref "SIM900-R7") (pin "2") (pinfunction "2_2") (pintype "passive"))
      (node (ref "STM-C1") (pin "2") (pinfunction "2_2") (pintype "passive"))
      (node (ref "STM-C10") (pin "1") (pinfunction "1_1") (pintype "passive"))
      (node (ref "STM-C11") (pin "1") (pinfunction "1_1") (pintype "passive"))
      (node (ref "STM-C12") (pin "1") (pinfunction "1_1") (pintype "passive"))
      (node (ref "STM-C13") (pin "1") (pinfunction "1_1") (pintype "passive"))
      (node (ref "STM-L1") (pin "1") (pinfunction "1_1") (pintype "passive"))
      (node (ref "STM-SWD") (pin "1") (pinfunction "1_1") (pintype "passive"))
      (node (ref "STM-USART") (pin "1") (pinfunction "1_1") (pintype "passive"))
      (node (ref "STM_CHIP") (pin "19") (pinfunction "VDD_4_19") (pintype "power_in"))
      (node (ref "STM_CHIP") (pin "32") (pinfunction "VDD_1_32") (pintype "power_in"))
      (node (ref "STM_CHIP") (pin "48") (pinfunction "VDD_2_48") (pintype "power_in"))
      (node (ref "STM_CHIP") (pin "64") (pinfunction "VDD_3_64") (pintype "power_in"))
      (node (ref "SYS-C3") (pin "1") (pinfunction "1_1") (pintype "passive"))
      (node (ref "SYS-R2") (pin "1") (pinfunction "1_1") (pintype "passive"))
      (node (ref "U$4") (pin "LCD_VCC") (pinfunction "LCD_VCC_LCD_VCC") (pintype "passive"))
      (node (ref "U2") (pin "28") (pinfunction "VDD_28") (pintype "passive"))
      (node (ref "W5500-C13") (pin "+") (pinfunction "+_+") (pintype "passive"))
      (node (ref "W5500-C5") (pin "1") (pinfunction "1_1") (pintype "passive"))
      (node (ref "W5500-R1") (pin "1") (pinfunction "1_1") (pintype "passive"))
      (node (ref "W5500-R13") (pin "2") (pinfunction "2_2") (pintype "passive"))
      (node (ref "W5500-R2") (pin "1") (pinfunction "1_1") (pintype "passive"))
      (node (ref "W5500-R3") (pin "1") (pinfunction "1_1") (pintype "passive"))
      (node (ref "W5500-R9") (pin "2") (pinfunction "2_2") (pintype "passive"))
    )
    (net (code "161") (name "VESP") (class "Default")
      (node (ref "ESP-C1") (pin "1") (pinfunction "1_1") (pintype "passive"))
      (node (ref "ESP-GPIO0") (pin "1") (pinfunction "1_1") (pintype "passive"))
      (node (ref "ESP-VDD") (pin "2") (pinfunction "2_2") (pintype "passive"))
      (node (ref "U$5") (pin "CH_PD") (pinfunction "CH_PD_CH_PD") (pintype "bidirectional"))
      (node (ref "U$5") (pin "VCC") (pinfunction "VCC_VCC") (pintype "power_in"))
    )
    (net (code "162") (name "VEXT") (class "Default")
      (node (ref "ESP-UART-A") (pin "1") (pinfunction "1_1") (pintype "passive"))
      (node (ref "ESP-VDD") (pin "3") (pinfunction "3_3") (pintype "passive"))
    )
    (net (code "163") (name "unconnected-(CT1-Pad3)") (class "Default")
      (node (ref "CT1") (pin "3") (pinfunction "3_3") (pintype "passive"))
    )
    (net (code "164") (name "unconnected-(CT1-Pad4)") (class "Default")
      (node (ref "CT1") (pin "4") (pinfunction "4_4") (pintype "passive"))
    )
    (net (code "165") (name "unconnected-(CT2-Pad3)") (class "Default")
      (node (ref "CT2") (pin "3") (pinfunction "3_3") (pintype "passive"))
    )
    (net (code "166") (name "unconnected-(CT2-Pad4)") (class "Default")
      (node (ref "CT2") (pin "4") (pinfunction "4_4") (pintype "passive"))
    )
    (net (code "167") (name "unconnected-(CT3-Pad3)") (class "Default")
      (node (ref "CT3") (pin "3") (pinfunction "3_3") (pintype "passive"))
    )
    (net (code "168") (name "unconnected-(CT3-Pad4)") (class "Default")
      (node (ref "CT3") (pin "4") (pinfunction "4_4") (pintype "passive"))
    )
    (net (code "169") (name "unconnected-(IC1-ADC-PadP$25)") (class "Default")
      (node (ref "IC1") (pin "P$25") (pinfunction "ADC_P$25") (pintype "bidirectional"))
    )
    (net (code "170") (name "unconnected-(IC1-CTS-PadP$7)") (class "Default")
      (node (ref "IC1") (pin "P$7") (pinfunction "CTS_P$7") (pintype "output"))
    )
    (net (code "171") (name "unconnected-(IC1-DBG_RXD-PadP$28)") (class "Default")
      (node (ref "IC1") (pin "P$28") (pinfunction "DBG_RXD_P$28") (pintype "input"))
    )
    (net (code "172") (name "unconnected-(IC1-DBG_TXD-PadP$27)") (class "Default")
      (node (ref "IC1") (pin "P$27") (pinfunction "DBG_TXD_P$27") (pintype "output"))
    )
    (net (code "173") (name "unconnected-(IC1-DCD-PadP$5)") (class "Default")
      (node (ref "IC1") (pin "P$5") (pinfunction "DCD_P$5") (pintype "output"))
    )
    (net (code "174") (name "unconnected-(IC1-DISP_CLK-PadP$11)") (class "Default")
      (node (ref "IC1") (pin "P$11") (pinfunction "DISP_CLK_P$11") (pintype "bidirectional"))
    )
    (net (code "175") (name "unconnected-(IC1-DISP_CS-PadP$14)") (class "Default")
      (node (ref "IC1") (pin "P$14") (pinfunction "DISP_CS_P$14") (pintype "bidirectional"))
    )
    (net (code "176") (name "unconnected-(IC1-DISP_DATA-PadP$12)") (class "Default")
      (node (ref "IC1") (pin "P$12") (pinfunction "DISP_DATA_P$12") (pintype "bidirectional"))
    )
    (net (code "177") (name "unconnected-(IC1-DISP_DC-PadP$13)") (class "Default")
      (node (ref "IC1") (pin "P$13") (pinfunction "DISP_DC_P$13") (pintype "bidirectional"))
    )
    (net (code "178") (name "unconnected-(IC1-DTR-PadP$3)") (class "Default")
      (node (ref "IC1") (pin "P$3") (pinfunction "DTR_P$3") (pintype "input"))
    )
    (net (code "179") (name "unconnected-(IC1-GPIO1{slash}KBR4-PadP$40)") (class "Default")
      (node (ref "IC1") (pin "P$40") (pinfunction "GPIO1/KBR4_P$40") (pintype "bidirectional"))
    )
    (net (code "180") (name "unconnected-(IC1-GPIO2{slash}KBR3-PadP$41)") (class "Default")
      (node (ref "IC1") (pin "P$41") (pinfunction "GPIO2/KBR3_P$41") (pintype "bidirectional"))
    )
    (net (code "181") (name "unconnected-(IC1-GPIO3{slash}KBR2-PadP$42)") (class "Default")
      (node (ref "IC1") (pin "P$42") (pinfunction "GPIO3/KBR2_P$42") (pintype "bidirectional"))
    )
    (net (code "182") (name "unconnected-(IC1-GPIO4{slash}KBR1-PadP$43)") (class "Default")
      (node (ref "IC1") (pin "P$43") (pinfunction "GPIO4/KBR1_P$43") (pintype "bidirectional"))
    )
    (net (code "183") (name "unconnected-(IC1-GPIO5{slash}KBR0-PadP$44)") (class "Default")
      (node (ref "IC1") (pin "P$44") (pinfunction "GPIO5/KBR0_P$44") (pintype "bidirectional"))
    )
    (net (code "184") (name "unconnected-(IC1-GPIO6{slash}KBC4-PadP$47)") (class "Default")
      (node (ref "IC1") (pin "P$47") (pinfunction "GPIO6/KBC4_P$47") (pintype "bidirectional"))
    )
    (net (code "185") (name "unconnected-(IC1-GPIO7{slash}KBC3-PadP$48)") (class "Default")
      (node (ref "IC1") (pin "P$48") (pinfunction "GPIO7/KBC3_P$48") (pintype "bidirectional"))
    )
    (net (code "186") (name "unconnected-(IC1-GPIO8{slash}KBC2-PadP$49)") (class "Default")
      (node (ref "IC1") (pin "P$49") (pinfunction "GPIO8/KBC2_P$49") (pintype "bidirectional"))
    )
    (net (code "187") (name "unconnected-(IC1-GPIO9{slash}KBC1-PadP$50)") (class "Default")
      (node (ref "IC1") (pin "P$50") (pinfunction "GPIO9/KBC1_P$50") (pintype "bidirectional"))
    )
    (net (code "188") (name "unconnected-(IC1-GPIO10-PadP$51)") (class "Default")
      (node (ref "IC1") (pin "P$51") (pinfunction "GPIO10_P$51") (pintype "bidirectional"))
    )
    (net (code "189") (name "unconnected-(IC1-LINEIN_L-PadP$24)") (class "Default")
      (node (ref "IC1") (pin "P$24") (pinfunction "LINEIN_L_P$24") (pintype "bidirectional"))
    )
    (net (code "190") (name "unconnected-(IC1-LINEIN_R-PadP$23)") (class "Default")
      (node (ref "IC1") (pin "P$23") (pinfunction "LINEIN_R_P$23") (pintype "bidirectional"))
    )
    (net (code "191") (name "unconnected-(IC1-MIC_N-PadP$20)") (class "Default")
      (node (ref "IC1") (pin "P$20") (pinfunction "MIC_N_P$20") (pintype "bidirectional"))
    )
    (net (code "192") (name "unconnected-(IC1-MIC_P-PadP$19)") (class "Default")
      (node (ref "IC1") (pin "P$19") (pinfunction "MIC_P_P$19") (pintype "bidirectional"))
    )
    (net (code "193") (name "unconnected-(IC1-NC-PadP$2)") (class "Default")
      (node (ref "IC1") (pin "P$2") (pinfunction "NC_P$2") (pintype "no_connect"))
    )
    (net (code "194") (name "unconnected-(IC1-NC-PadP$6)") (class "Default")
      (node (ref "IC1") (pin "P$6") (pinfunction "NC_P$6") (pintype "no_connect"))
    )
    (net (code "195") (name "unconnected-(IC1-PWM1-PadP$35)") (class "Default")
      (node (ref "IC1") (pin "P$35") (pinfunction "PWM1_P$35") (pintype "bidirectional"))
    )
    (net (code "196") (name "unconnected-(IC1-PWM2-PadP$36)") (class "Default")
      (node (ref "IC1") (pin "P$36") (pinfunction "PWM2_P$36") (pintype "bidirectional"))
    )
    (net (code "197") (name "unconnected-(IC1-RI-PadP$4)") (class "Default")
      (node (ref "IC1") (pin "P$4") (pinfunction "RI_P$4") (pintype "output"))
    )
    (net (code "198") (name "unconnected-(IC1-RTS-PadP$8)") (class "Default")
      (node (ref "IC1") (pin "P$8") (pinfunction "RTS_P$8") (pintype "input"))
    )
    (net (code "199") (name "unconnected-(IC1-SCL-PadP$38)") (class "Default")
      (node (ref "IC1") (pin "P$38") (pinfunction "SCL_P$38") (pintype "bidirectional"))
    )
    (net (code "200") (name "unconnected-(IC1-SDA-PadP$37)") (class "Default")
      (node (ref "IC1") (pin "P$37") (pinfunction "SDA_P$37") (pintype "bidirectional"))
    )
    (net (code "201") (name "unconnected-(IC1-SIM_PRESENCE-PadP$34)") (class "Default")
      (node (ref "IC1") (pin "P$34") (pinfunction "SIM_PRESENCE_P$34") (pintype "bidirectional"))
    )
    (net (code "202") (name "unconnected-(IC1-SPK_N-PadP$22)") (class "Default")
      (node (ref "IC1") (pin "P$22") (pinfunction "SPK_N_P$22") (pintype "bidirectional"))
    )
    (net (code "203") (name "unconnected-(IC1-SPK_P-PadP$21)") (class "Default")
      (node (ref "IC1") (pin "P$21") (pinfunction "SPK_P_P$21") (pintype "bidirectional"))
    )
    (net (code "204") (name "unconnected-(IC1-VDD_EXT-PadP$15)") (class "Default")
      (node (ref "IC1") (pin "P$15") (pinfunction "VDD_EXT_P$15") (pintype "bidirectional"))
    )
    (net (code "205") (name "unconnected-(IC5A-QE-Pad4)") (class "Default")
      (node (ref "IC5") (pin "4") (pinfunction "QE_4") (pintype "tri_state"))
    )
    (net (code "206") (name "unconnected-(IC5A-QF-Pad5)") (class "Default")
      (node (ref "IC5") (pin "5") (pinfunction "QF_5") (pintype "tri_state"))
    )
    (net (code "207") (name "unconnected-(IC5A-QG-Pad6)") (class "Default")
      (node (ref "IC5") (pin "6") (pinfunction "QG_6") (pintype "tri_state"))
    )
    (net (code "208") (name "unconnected-(IC5A-QH*-Pad9)") (class "Default")
      (node (ref "IC5") (pin "9") (pinfunction "QH*_9") (pintype "tri_state"))
    )
    (net (code "209") (name "unconnected-(IC5A-QH-Pad7)") (class "Default")
      (node (ref "IC5") (pin "7") (pinfunction "QH_7") (pintype "tri_state"))
    )
    (net (code "210") (name "unconnected-(SENSOR-DHT-Pad3)") (class "Default")
      (node (ref "SENSOR-DHT") (pin "3") (pinfunction "3_3") (pintype "passive"))
    )
    (net (code "211") (name "unconnected-(SIM_HOLDER-VPP-Pad5)") (class "Default")
      (node (ref "SIM_HOLDER") (pin "5") (pinfunction "VPP_5") (pintype "bidirectional"))
    )
    (net (code "212") (name "unconnected-(STM_CHIP-BOOT0-Pad60)") (class "Default")
      (node (ref "STM_CHIP") (pin "60") (pinfunction "BOOT0_60") (pintype "input"))
    )
    (net (code "213") (name "unconnected-(STM_CHIP-PA0-WKUP1-Pad14)") (class "Default")
      (node (ref "STM_CHIP") (pin "14") (pinfunction "PA0-WKUP1_14") (pintype "bidirectional"))
    )
    (net (code "214") (name "unconnected-(STM_CHIP-PA8-Pad41)") (class "Default")
      (node (ref "STM_CHIP") (pin "41") (pinfunction "PA8_41") (pintype "bidirectional"))
    )
    (net (code "215") (name "unconnected-(STM_CHIP-PA11-Pad44)") (class "Default")
      (node (ref "STM_CHIP") (pin "44") (pinfunction "PA11_44") (pintype "bidirectional"))
    )
    (net (code "216") (name "unconnected-(STM_CHIP-PA12-Pad45)") (class "Default")
      (node (ref "STM_CHIP") (pin "45") (pinfunction "PA12_45") (pintype "bidirectional"))
    )
    (net (code "217") (name "unconnected-(STM_CHIP-PB2-Pad28)") (class "Default")
      (node (ref "STM_CHIP") (pin "28") (pinfunction "PB2_28") (pintype "bidirectional"))
    )
    (net (code "218") (name "unconnected-(STM_CHIP-PB3-Pad55)") (class "Default")
      (node (ref "STM_CHIP") (pin "55") (pinfunction "PB3_55") (pintype "bidirectional"))
    )
    (net (code "219") (name "unconnected-(STM_CHIP-PB11-Pad30)") (class "Default")
      (node (ref "STM_CHIP") (pin "30") (pinfunction "PB11_30") (pintype "bidirectional"))
    )
    (net (code "220") (name "unconnected-(STM_CHIP-PC7-Pad38)") (class "Default")
      (node (ref "STM_CHIP") (pin "38") (pinfunction "PC7_38") (pintype "bidirectional"))
    )
    (net (code "221") (name "unconnected-(STM_CHIP-PC8-Pad39)") (class "Default")
      (node (ref "STM_CHIP") (pin "39") (pinfunction "PC8_39") (pintype "bidirectional"))
    )
    (net (code "222") (name "unconnected-(STM_CHIP-PC13-RTC_AF1-WKUP2-Pad2)") (class "Default")
      (node (ref "STM_CHIP") (pin "2") (pinfunction "PC13-RTC_AF1-WKUP2_2") (pintype "bidirectional"))
    )
    (net (code "223") (name "unconnected-(STM_CHIP-PH0_-OSC_IN-Pad5)") (class "Default")
      (node (ref "STM_CHIP") (pin "5") (pinfunction "PH0_-OSC_IN_5") (pintype "bidirectional"))
    )
    (net (code "224") (name "unconnected-(STM_CHIP-PH1-_OSC_OUT-Pad6)") (class "Default")
      (node (ref "STM_CHIP") (pin "6") (pinfunction "PH1-_OSC_OUT_6") (pintype "bidirectional"))
    )
    (net (code "225") (name "unconnected-(U$5-GPIO2-PadGPIO02)") (class "Default")
      (node (ref "U$5") (pin "GPIO02") (pinfunction "GPIO2_GPIO02") (pintype "bidirectional"))
    )
    (net (code "226") (name "unconnected-(U$5-GPIO4-PadGPIO04)") (class "Default")
      (node (ref "U$5") (pin "GPIO04") (pinfunction "GPIO4_GPIO04") (pintype "bidirectional"))
    )
    (net (code "227") (name "unconnected-(U$5-GPIO5-PadGPIO05)") (class "Default")
      (node (ref "U$5") (pin "GPIO05") (pinfunction "GPIO5_GPIO05") (pintype "bidirectional"))
    )
    (net (code "228") (name "unconnected-(U$5-PadADC)") (class "Default")
      (node (ref "U$5") (pin "ADC") (pinfunction "ADC_ADC") (pintype "bidirectional"))
    )
    (net (code "229") (name "unconnected-(U$5-PadGPIO12)") (class "Default")
      (node (ref "U$5") (pin "GPIO12") (pinfunction "GPIO12_GPIO12") (pintype "bidirectional"))
    )
    (net (code "230") (name "unconnected-(U$5-PadGPIO13)") (class "Default")
      (node (ref "U$5") (pin "GPIO13") (pinfunction "GPIO13_GPIO13") (pintype "bidirectional"))
    )
    (net (code "231") (name "unconnected-(U$5-PadGPIO14)") (class "Default")
      (node (ref "U$5") (pin "GPIO14") (pinfunction "GPIO14_GPIO14") (pintype "bidirectional"))
    )
    (net (code "232") (name "unconnected-(U$5-PadGPIO16)") (class "Default")
      (node (ref "U$5") (pin "GPIO16") (pinfunction "GPIO16_GPIO16") (pintype "bidirectional"))
    )
    (net (code "233") (name "unconnected-(U$5-PadREST)") (class "Default")
      (node (ref "U$5") (pin "REST") (pinfunction "REST_REST") (pintype "bidirectional"))
    )
    (net (code "234") (name "unconnected-(U2-DNC-Pad7)") (class "Default")
      (node (ref "U2") (pin "7") (pinfunction "DNC_7") (pintype "passive"))
    )
    (net (code "235") (name "unconnected-(U2-DUPLED-Pad26)") (class "Default")
      (node (ref "U2") (pin "26") (pinfunction "DUPLED_26") (pintype "passive"))
    )
    (net (code "236") (name "unconnected-(U2-INT_N-Pad36)") (class "Default")
      (node (ref "U2") (pin "36") (pinfunction "INT_N_36") (pintype "passive"))
    )
    (net (code "237") (name "unconnected-(U2-NC-Pad12)") (class "Default")
      (node (ref "U2") (pin "12") (pinfunction "NC_12") (pintype "passive"))
    )
    (net (code "238") (name "unconnected-(U2-NC-Pad13)") (class "Default")
      (node (ref "U2") (pin "13") (pinfunction "NC_13") (pintype "passive"))
    )
    (net (code "239") (name "unconnected-(U2-NC-Pad46)") (class "Default")
      (node (ref "U2") (pin "46") (pinfunction "NC_46") (pintype "passive"))
    )
    (net (code "240") (name "unconnected-(U2-NC-Pad47)") (class "Default")
      (node (ref "U2") (pin "47") (pinfunction "NC_47") (pintype "passive"))
    )
    (net (code "241") (name "unconnected-(U2-SPDLED-Pad24)") (class "Default")
      (node (ref "U2") (pin "24") (pinfunction "SPDLED_24") (pintype "passive"))
    )
    (net (code "242") (name "unconnected-(U2-VBG-Pad18)") (class "Default")
      (node (ref "U2") (pin "18") (pinfunction "VBG_18") (pintype "passive"))
    )
  )
)
